# design.net
KiCad netlist of a schematic drawn in Altium Designer
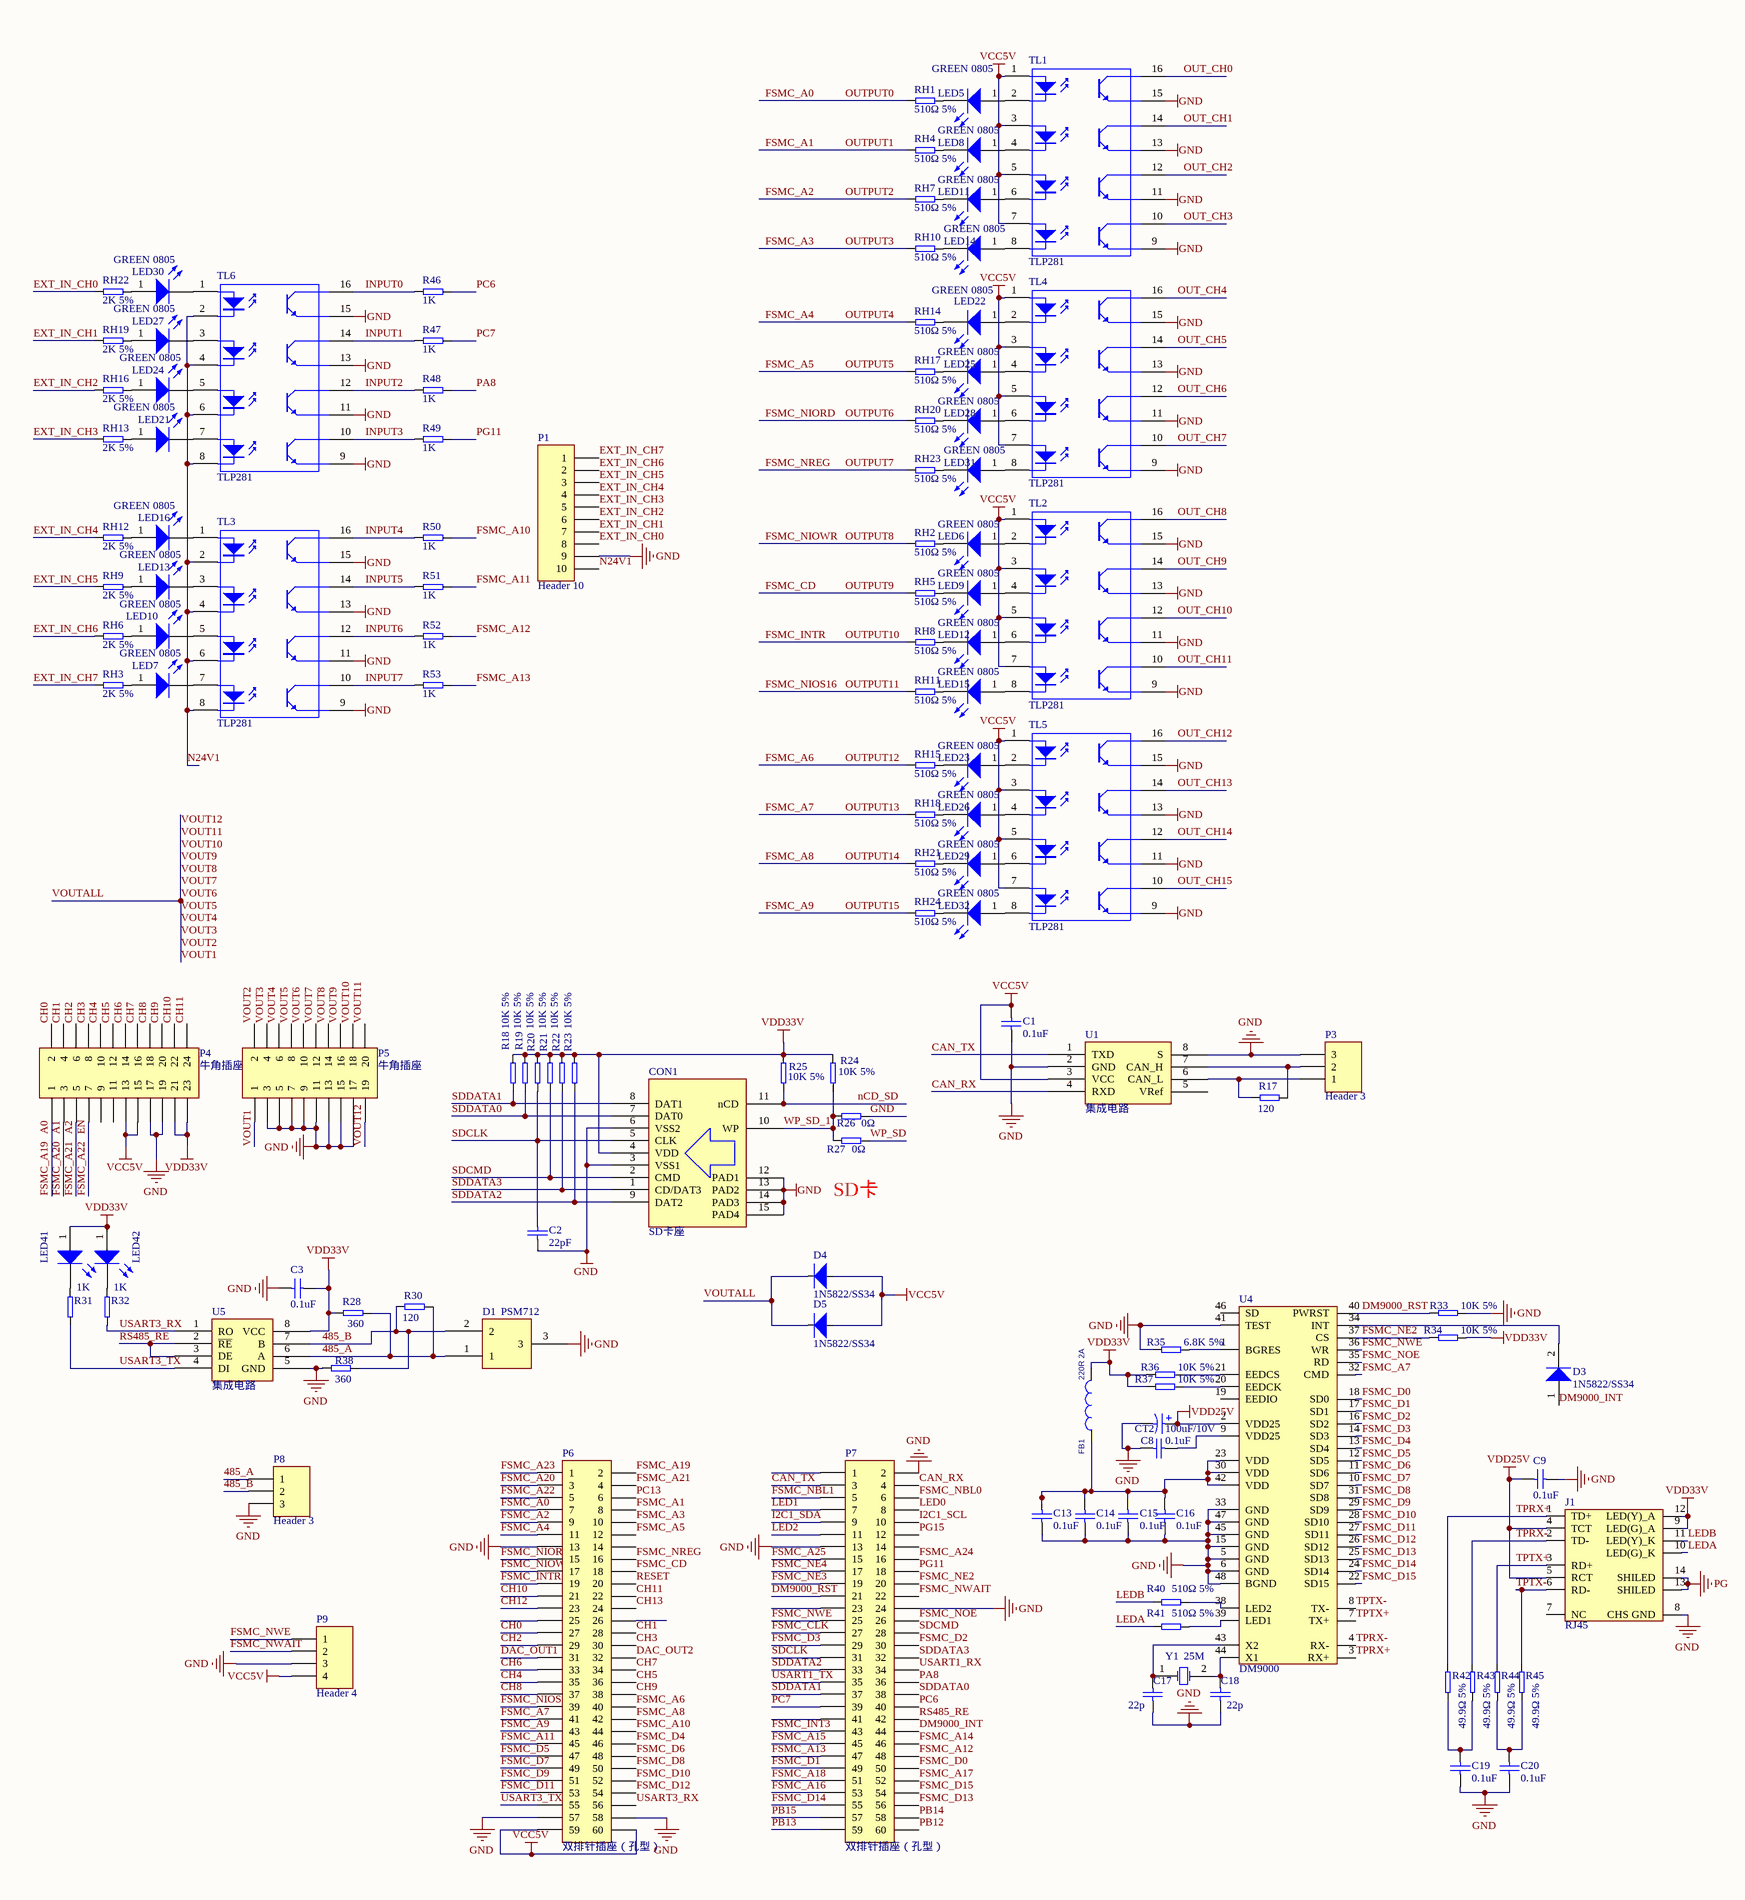
[diagram p0: 电眼主板.SchDoc, left]
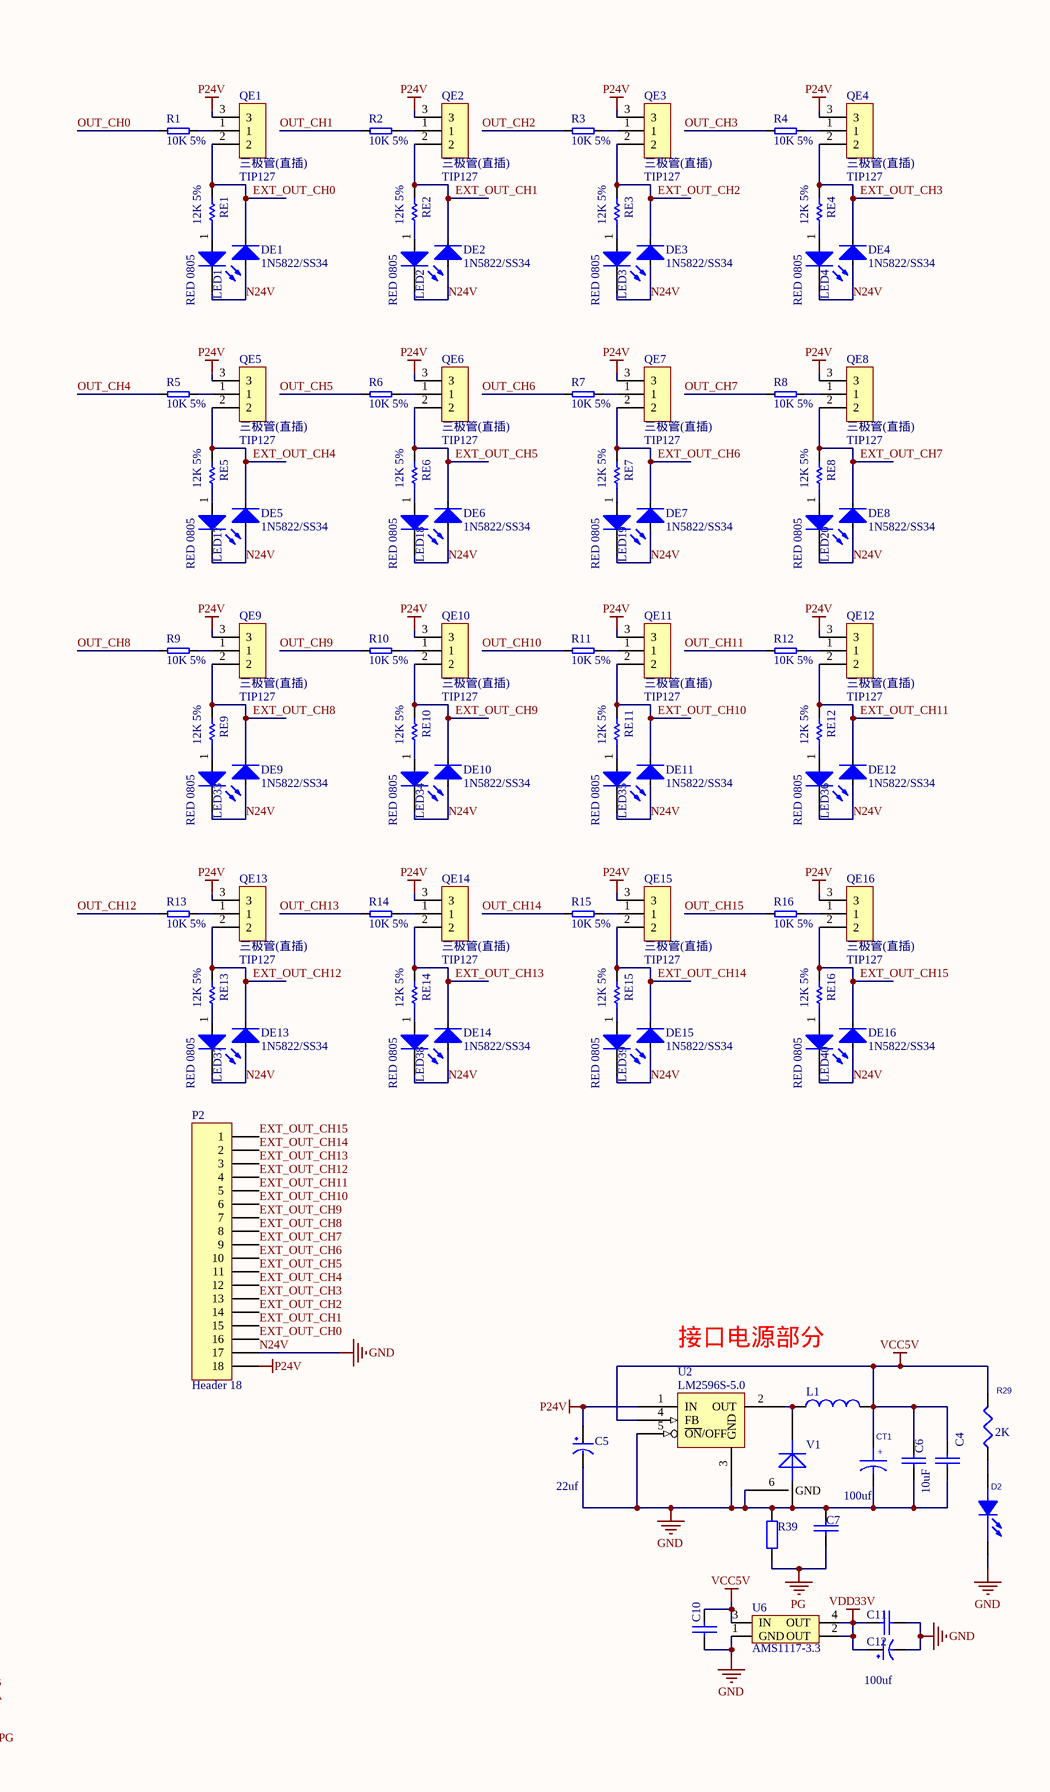
[diagram p1: 电眼主板.SchDoc, right]

(export (version "E")
  (design (tool "Eeschema 10.0.6"))
  (components
    (comp (ref "C1")
      (value "0.1uF")
      (footprint "0603")
      (description "0603X7R104J160NT(0.1uF)")
      (fields (field (name "Comment") "电容(贴片)"))
      (libsource (lib "altium-import") (part "root_3_CAP_0.1uF X7R 0603_"))
    )
    (comp (ref "C2")
      (value "22pF")
      (footprint "0603")
      (description "0603COG220J500NT(22pF)")
      (fields (field (name "Comment") "电容(贴片)"))
      (libsource (lib "altium-import") (part "root_1_CAP_22pF COG 0603_"))
    )
    (comp (ref "C3")
      (value "0.1uF")
      (footprint "0603")
      (description "0603X7R104J160NT(0.1uF)")
      (fields (field (name "Comment") "电容(贴片)"))
      (libsource (lib "altium-import") (part "root_0_CAP_0.1uF X7R 0603_"))
    )
    (comp (ref "C4")
      (value "电容(贴片)")
      (footprint "0805C")
      (description "'0603X7R104J160NT(0.1uF)")
      (libsource (lib "*") (part "CAP"))
    )
    (comp (ref "C5")
      (value "22uf")
      (footprint "CC6.56.5")
      (description "35TZV22M5X6.1")
      (fields (field (name "Comment") "电解电容(贴片)"))
      (libsource (lib "") (part "CAP_1"))
    )
    (comp (ref "C6")
      (value "10uF")
      (footprint "0805C")
      (description "片状电容")
      (libsource (lib "*") (part "Pro92D1.TMP_105_9"))
    )
    (comp (ref "C7") (value "102/2KV") (footprint "0805CC") (libsource (lib "*") (part "CAP")))
    (comp (ref "C8")
      (value "0.1uF")
      (footprint "0603")
      (description "0603X7R104J160NT(0.1uF)")
      (fields (field (name "Comment") "电容(贴片)"))
      (libsource (lib "altium-import") (part "root_0_mirrored_CAP_0.1uF X7R 0603_"))
    )
    (comp (ref "C9")
      (value "0.1uF")
      (footprint "0603")
      (description "0603X7R104J160NT(0.1uF)")
      (fields (field (name "Comment") "电容(贴片)"))
      (libsource (lib "altium-import") (part "root_2_CAP_0.1uF X7R 0603_"))
    )
    (comp (ref "C10")
      (value "电容(贴片)")
      (footprint "0805C")
      (description "'0603X7R104J160NT(0.1uF)")
      (libsource (lib "*") (part "CAP"))
    )
    (comp (ref "C11")
      (value "电容(贴片)")
      (footprint "0805C")
      (description "'0603X7R104J160NT(0.1uF)")
      (libsource (lib "*") (part "CAP"))
    )
    (comp (ref "C12")
      (value "100uf")
      (footprint "CC6.56.5")
      (description "10SEV100M6.3X5.5")
      (fields (field (name "Comment") "电解电容(贴片)"))
      (libsource (lib "WarShip V3 STM32103封装库") (part "CAP"))
    )
    (comp (ref "C13")
      (value "0.1uF")
      (footprint "0603")
      (description "0603X7R104J160NT(0.1uF)")
      (fields (field (name "Comment") "电容(贴片)"))
      (libsource (lib "altium-import") (part "root_1_CAP_0.1uF X7R 0603_"))
    )
    (comp (ref "C14")
      (value "0.1uF")
      (footprint "0603")
      (description "0603X7R104J160NT(0.1uF)")
      (fields (field (name "Comment") "电容(贴片)"))
      (libsource (lib "altium-import") (part "root_1_CAP_0.1uF X7R 0603_"))
    )
    (comp (ref "C15")
      (value "0.1uF")
      (footprint "0603")
      (description "0603X7R104J160NT(0.1uF)")
      (fields (field (name "Comment") "电容(贴片)"))
      (libsource (lib "altium-import") (part "root_1_CAP_0.1uF X7R 0603_"))
    )
    (comp (ref "C16")
      (value "0.1uF")
      (footprint "0603")
      (description "0603X7R104J160NT(0.1uF)")
      (fields (field (name "Comment") "电容(贴片)"))
      (libsource (lib "altium-import") (part "root_1_CAP_0.1uF X7R 0603_"))
    )
    (comp (ref "C17")
      (value "22p")
      (footprint "0603")
      (description "Capacitor 22p")
      (fields (field (name "Comment") "电容(贴片)") (field (name "PUBLISHER") "Altium Limited"))
      (libsource (lib "Miscellaneous Devices") (part "Cap"))
    )
    (comp (ref "C18")
      (value "22p")
      (footprint "0603")
      (description "Capacitor 22p")
      (fields (field (name "Comment") "电容(贴片)") (field (name "PUBLISHER") "Altium Limited"))
      (libsource (lib "Miscellaneous Devices") (part "Cap"))
    )
    (comp (ref "C19")
      (value "0.1uF")
      (footprint "0603")
      (description "0603X7R104J160NT(0.1uF)")
      (fields (field (name "Comment") "电容(贴片)"))
      (libsource (lib "altium-import") (part "root_1_CAP_0.1uF X7R 0603_"))
    )
    (comp (ref "C20")
      (value "0.1uF")
      (footprint "0603")
      (description "0603X7R104J160NT(0.1uF)")
      (fields (field (name "Comment") "电容(贴片)"))
      (libsource (lib "altium-import") (part "root_1_CAP_0.1uF X7R 0603_"))
    )
    (comp (ref "CON1")
      (value "SD卡座")
      (footprint "SDCARD")
      (description "SD/MMC CARD 26mm*25mm")
      (libsource (lib "altium-import") (part "root_0_SD-CARD_"))
    )
    (comp (ref "CT1")
      (value "100uf")
      (footprint "CT7343")
      (description "CAP TANTALUM 100UF 16V 20% SMD")
      (fields (field (name "VENDOR PART#") "495-2256-1-ND") (field (name "MFG PART#") "B45196H3107M409"))
      (libsource (lib "*") (part "CAP POL"))
    )
    (comp (ref "CT2")
      (value "100uF/10V")
      (footprint "6032")
      (description "CAP TANTALUM 100UF 16V 20% SMD")
      (fields (field (name "Comment") "钽电容"))
      (libsource (lib "altium-import") (part "root_1_mirrored_CAP TAN 100uF/10V/6032_"))
    )
    (comp (ref "D1") (value "PSM712") (footprint "SOT-23") (libsource (lib "PSM712") (part "Component_1")))
    (comp (ref "D2")
      (value "二极管(贴片发光红色)")
      (description "17-215-SURC-S530-A3-TR8")
      (fields (field (name "VENDOR PART#") "160-1426-1-ND") (field (name "MFG PART#") "LTST-C171KGKT"))
      (libsource (lib "*") (part "LED"))
    )
    (comp (ref "D3")
      (value "1N5822/SS34")
      (footprint "D1206")
      (description "1N4148/1206")
      (fields (field (name "Comment") "二极管(贴片)"))
      (libsource (lib "altium-import") (part "root_3_mirrored_DIODE 1N4148/1206_"))
    )
    (comp (ref "D4")
      (value "1N5822/SS34")
      (footprint "D1206")
      (description "1N5822/SS34/SMA 肖特基")
      (fields (field (name "Comment") "二极管(贴片)"))
      (libsource (lib "SCH_XIJUN") (part "DIODE 1N5822/SS34"))
    )
    (comp (ref "D5")
      (value "1N5822/SS34")
      (footprint "D1206")
      (description "1N5822/SS34/SMA 肖特基")
      (fields (field (name "Comment") "二极管(贴片)"))
      (libsource (lib "SCH_XIJUN") (part "DIODE 1N5822/SS34"))
    )
    (comp (ref "DE1")
      (value "1N5822/SS34")
      (footprint "D1206")
      (description "1N5822/SS34/SMA 肖特基")
      (fields (field (name "Comment") "二极管(贴片)"))
      (libsource (lib "SCH_XIJUN") (part "DIODE 1N5822/SS34"))
    )
    (comp (ref "DE2")
      (value "1N5822/SS34")
      (footprint "D1206")
      (description "1N5822/SS34/SMA 肖特基")
      (fields (field (name "Comment") "二极管(贴片)"))
      (libsource (lib "SCH_XIJUN") (part "DIODE 1N5822/SS34"))
    )
    (comp (ref "DE3")
      (value "1N5822/SS34")
      (footprint "D1206")
      (description "1N5822/SS34/SMA 肖特基")
      (fields (field (name "Comment") "二极管(贴片)"))
      (libsource (lib "SCH_XIJUN") (part "DIODE 1N5822/SS34"))
    )
    (comp (ref "DE4")
      (value "1N5822/SS34")
      (footprint "D1206")
      (description "1N5822/SS34/SMA 肖特基")
      (fields (field (name "Comment") "二极管(贴片)"))
      (libsource (lib "SCH_XIJUN") (part "DIODE 1N5822/SS34"))
    )
    (comp (ref "DE5")
      (value "1N5822/SS34")
      (footprint "D1206")
      (description "1N5822/SS34/SMA 肖特基")
      (fields (field (name "Comment") "二极管(贴片)"))
      (libsource (lib "SCH_XIJUN") (part "DIODE 1N5822/SS34"))
    )
    (comp (ref "DE6")
      (value "1N5822/SS34")
      (footprint "D1206")
      (description "1N5822/SS34/SMA 肖特基")
      (fields (field (name "Comment") "二极管(贴片)"))
      (libsource (lib "SCH_XIJUN") (part "DIODE 1N5822/SS34"))
    )
    (comp (ref "DE7")
      (value "1N5822/SS34")
      (footprint "D1206")
      (description "1N5822/SS34/SMA 肖特基")
      (fields (field (name "Comment") "二极管(贴片)"))
      (libsource (lib "SCH_XIJUN") (part "DIODE 1N5822/SS34"))
    )
    (comp (ref "DE8")
      (value "1N5822/SS34")
      (footprint "D1206")
      (description "1N5822/SS34/SMA 肖特基")
      (fields (field (name "Comment") "二极管(贴片)"))
      (libsource (lib "SCH_XIJUN") (part "DIODE 1N5822/SS34"))
    )
    (comp (ref "DE9")
      (value "1N5822/SS34")
      (footprint "D1206")
      (description "1N5822/SS34/SMA 肖特基")
      (fields (field (name "Comment") "二极管(贴片)"))
      (libsource (lib "SCH_XIJUN") (part "DIODE 1N5822/SS34"))
    )
    (comp (ref "DE10")
      (value "1N5822/SS34")
      (footprint "D1206")
      (description "1N5822/SS34/SMA 肖特基")
      (fields (field (name "Comment") "二极管(贴片)"))
      (libsource (lib "SCH_XIJUN") (part "DIODE 1N5822/SS34"))
    )
    (comp (ref "DE11")
      (value "1N5822/SS34")
      (footprint "D1206")
      (description "1N5822/SS34/SMA 肖特基")
      (fields (field (name "Comment") "二极管(贴片)"))
      (libsource (lib "SCH_XIJUN") (part "DIODE 1N5822/SS34"))
    )
    (comp (ref "DE12")
      (value "1N5822/SS34")
      (footprint "D1206")
      (description "1N5822/SS34/SMA 肖特基")
      (fields (field (name "Comment") "二极管(贴片)"))
      (libsource (lib "SCH_XIJUN") (part "DIODE 1N5822/SS34"))
    )
    (comp (ref "DE13")
      (value "1N5822/SS34")
      (footprint "D1206")
      (description "1N5822/SS34/SMA 肖特基")
      (fields (field (name "Comment") "二极管(贴片)"))
      (libsource (lib "SCH_XIJUN") (part "DIODE 1N5822/SS34"))
    )
    (comp (ref "DE14")
      (value "1N5822/SS34")
      (footprint "D1206")
      (description "1N5822/SS34/SMA 肖特基")
      (fields (field (name "Comment") "二极管(贴片)"))
      (libsource (lib "SCH_XIJUN") (part "DIODE 1N5822/SS34"))
    )
    (comp (ref "DE15")
      (value "1N5822/SS34")
      (footprint "D1206")
      (description "1N5822/SS34/SMA 肖特基")
      (fields (field (name "Comment") "二极管(贴片)"))
      (libsource (lib "SCH_XIJUN") (part "DIODE 1N5822/SS34"))
    )
    (comp (ref "DE16")
      (value "1N5822/SS34")
      (footprint "D1206")
      (description "1N5822/SS34/SMA 肖特基")
      (fields (field (name "Comment") "二极管(贴片)"))
      (libsource (lib "SCH_XIJUN") (part "DIODE 1N5822/SS34"))
    )
    (comp (ref "FB1")
      (value "220R 2A")
      (description "220R,2.0A,0.05DCR")
      (fields (field (name "MFG") "Murata") (field (name "MFG PART#") "BLM18PG121SN1D"))
      (libsource (lib "*") (part "FERRITE"))
    )
    (comp (ref "J1")
      (value "RJ45")
      (footprint "HR911105A")
      (description "HR911105A")
      (libsource (lib "WarShip V3 STM32103封装库") (part "HR911105"))
    )
    (comp (ref "L1")
      (value "电感(贴片)")
      (footprint "6045")
      (description "PRS6045-330MT")
      (fields (field (name "PUBLISHER") "Altium Limited"))
      (libsource (lib "Miscellaneous Devices") (part "Inductor"))
    )
    (comp (ref "LED1")
      (value "RED 0805")
      (footprint "LED-0805")
      (description "'17-215-SURC-S530-A3-TR8")
      (fields (field (name "Comment") "二极管(贴片发光红色)"))
      (libsource (lib "SCH_XIJUN") (part "LED_GREEN 0805"))
    )
    (comp (ref "LED2")
      (value "RED 0805")
      (footprint "LED-0805")
      (description "'17-215-SURC-S530-A3-TR8")
      (fields (field (name "Comment") "二极管(贴片发光红色)"))
      (libsource (lib "SCH_XIJUN") (part "LED_GREEN 0805"))
    )
    (comp (ref "LED3")
      (value "RED 0805")
      (footprint "LED-0805")
      (description "'17-215-SURC-S530-A3-TR8")
      (fields (field (name "Comment") "二极管(贴片发光红色)"))
      (libsource (lib "SCH_XIJUN") (part "LED_GREEN 0805"))
    )
    (comp (ref "LED4")
      (value "RED 0805")
      (footprint "LED-0805")
      (description "'17-215-SURC-S530-A3-TR8")
      (fields (field (name "Comment") "二极管(贴片发光红色)"))
      (libsource (lib "SCH_XIJUN") (part "LED_GREEN 0805"))
    )
    (comp (ref "LED5")
      (value "GREEN 0805")
      (footprint "LED-0805")
      (description "黄色LED")
      (fields (field (name "Comment") "二极管(贴片发光黄色)"))
      (libsource (lib "SCH_XIJUN") (part "LED_GREEN 0805"))
    )
    (comp (ref "LED6")
      (value "GREEN 0805")
      (footprint "LED-0805")
      (description "黄色LED")
      (fields (field (name "Comment") "二极管(贴片发光黄色)"))
      (libsource (lib "SCH_XIJUN") (part "LED_GREEN 0805"))
    )
    (comp (ref "LED7")
      (value "GREEN 0805")
      (footprint "LED-0805")
      (description "17-215SYGC-S530-E2-TR8")
      (fields (field (name "Comment") "二极管(贴片发光绿色)"))
      (libsource (lib "SCH_XIJUN") (part "LED_GREEN 0805"))
    )
    (comp (ref "LED8")
      (value "GREEN 0805")
      (footprint "LED-0805")
      (description "黄色LED")
      (fields (field (name "Comment") "二极管(贴片发光黄色)"))
      (libsource (lib "SCH_XIJUN") (part "LED_GREEN 0805"))
    )
    (comp (ref "LED9")
      (value "GREEN 0805")
      (footprint "LED-0805")
      (description "黄色LED")
      (fields (field (name "Comment") "二极管(贴片发光黄色)"))
      (libsource (lib "SCH_XIJUN") (part "LED_GREEN 0805"))
    )
    (comp (ref "LED10")
      (value "GREEN 0805")
      (footprint "LED-0805")
      (description "17-215SYGC-S530-E2-TR8")
      (fields (field (name "Comment") "二极管(贴片发光绿色)"))
      (libsource (lib "SCH_XIJUN") (part "LED_GREEN 0805"))
    )
    (comp (ref "LED11")
      (value "GREEN 0805")
      (footprint "LED-0805")
      (description "黄色LED")
      (fields (field (name "Comment") "二极管(贴片发光黄色)"))
      (libsource (lib "SCH_XIJUN") (part "LED_GREEN 0805"))
    )
    (comp (ref "LED12")
      (value "GREEN 0805")
      (footprint "LED-0805")
      (description "黄色LED")
      (fields (field (name "Comment") "二极管(贴片发光黄色)"))
      (libsource (lib "SCH_XIJUN") (part "LED_GREEN 0805"))
    )
    (comp (ref "LED13")
      (value "GREEN 0805")
      (footprint "LED-0805")
      (description "17-215SYGC-S530-E2-TR8")
      (fields (field (name "Comment") "二极管(贴片发光绿色)"))
      (libsource (lib "SCH_XIJUN") (part "LED_GREEN 0805"))
    )
    (comp (ref "LED14")
      (value "GREEN 0805")
      (footprint "LED-0805")
      (description "黄色LED")
      (fields (field (name "Comment") "二极管(贴片发光黄色)"))
      (libsource (lib "SCH_XIJUN") (part "LED_GREEN 0805"))
    )
    (comp (ref "LED15")
      (value "GREEN 0805")
      (footprint "LED-0805")
      (description "黄色LED")
      (fields (field (name "Comment") "二极管(贴片发光黄色)"))
      (libsource (lib "SCH_XIJUN") (part "LED_GREEN 0805"))
    )
    (comp (ref "LED16")
      (value "GREEN 0805")
      (footprint "LED-0805")
      (description "17-215SYGC-S530-E2-TR8")
      (fields (field (name "Comment") "二极管(贴片发光绿色)"))
      (libsource (lib "SCH_XIJUN") (part "LED_GREEN 0805"))
    )
    (comp (ref "LED17")
      (value "RED 0805")
      (footprint "LED-0805")
      (description "'17-215-SURC-S530-A3-TR8")
      (fields (field (name "Comment") "二极管(贴片发光红色)"))
      (libsource (lib "SCH_XIJUN") (part "LED_GREEN 0805"))
    )
    (comp (ref "LED18")
      (value "RED 0805")
      (footprint "LED-0805")
      (description "'17-215-SURC-S530-A3-TR8")
      (fields (field (name "Comment") "二极管(贴片发光红色)"))
      (libsource (lib "SCH_XIJUN") (part "LED_GREEN 0805"))
    )
    (comp (ref "LED19")
      (value "RED 0805")
      (footprint "LED-0805")
      (description "'17-215-SURC-S530-A3-TR8")
      (fields (field (name "Comment") "二极管(贴片发光红色)"))
      (libsource (lib "SCH_XIJUN") (part "LED_GREEN 0805"))
    )
    (comp (ref "LED20")
      (value "RED 0805")
      (footprint "LED-0805")
      (description "'17-215-SURC-S530-A3-TR8")
      (fields (field (name "Comment") "二极管(贴片发光红色)"))
      (libsource (lib "SCH_XIJUN") (part "LED_GREEN 0805"))
    )
    (comp (ref "LED21")
      (value "GREEN 0805")
      (footprint "LED-0805")
      (description "17-215SYGC-S530-E2-TR8")
      (fields (field (name "Comment") "二极管(贴片发光绿色)"))
      (libsource (lib "SCH_XIJUN") (part "LED_GREEN 0805"))
    )
    (comp (ref "LED22")
      (value "GREEN 0805")
      (footprint "LED-0805")
      (description "黄色LED")
      (fields (field (name "Comment") "二极管(贴片发光黄色)"))
      (libsource (lib "SCH_XIJUN") (part "LED_GREEN 0805"))
    )
    (comp (ref "LED23")
      (value "GREEN 0805")
      (footprint "LED-0805")
      (description "黄色LED")
      (fields (field (name "Comment") "二极管(贴片发光黄色)"))
      (libsource (lib "SCH_XIJUN") (part "LED_GREEN 0805"))
    )
    (comp (ref "LED24")
      (value "GREEN 0805")
      (footprint "LED-0805")
      (description "17-215SYGC-S530-E2-TR8")
      (fields (field (name "Comment") "二极管(贴片发光绿色)"))
      (libsource (lib "SCH_XIJUN") (part "LED_GREEN 0805"))
    )
    (comp (ref "LED25")
      (value "GREEN 0805")
      (footprint "LED-0805")
      (description "黄色LED")
      (fields (field (name "Comment") "二极管(贴片发光黄色)"))
      (libsource (lib "SCH_XIJUN") (part "LED_GREEN 0805"))
    )
    (comp (ref "LED26")
      (value "GREEN 0805")
      (footprint "LED-0805")
      (description "黄色LED")
      (fields (field (name "Comment") "二极管(贴片发光黄色)"))
      (libsource (lib "SCH_XIJUN") (part "LED_GREEN 0805"))
    )
    (comp (ref "LED27")
      (value "GREEN 0805")
      (footprint "LED-0805")
      (description "17-215SYGC-S530-E2-TR8")
      (fields (field (name "Comment") "二极管(贴片发光绿色)"))
      (libsource (lib "SCH_XIJUN") (part "LED_GREEN 0805"))
    )
    (comp (ref "LED28")
      (value "GREEN 0805")
      (footprint "LED-0805")
      (description "黄色LED")
      (fields (field (name "Comment") "二极管(贴片发光黄色)"))
      (libsource (lib "SCH_XIJUN") (part "LED_GREEN 0805"))
    )
    (comp (ref "LED29")
      (value "GREEN 0805")
      (footprint "LED-0805")
      (description "黄色LED")
      (fields (field (name "Comment") "二极管(贴片发光黄色)"))
      (libsource (lib "SCH_XIJUN") (part "LED_GREEN 0805"))
    )
    (comp (ref "LED30")
      (value "GREEN 0805")
      (footprint "LED-0805")
      (description "17-215SYGC-S530-E2-TR8")
      (fields (field (name "Comment") "二极管(贴片发光绿色)"))
      (libsource (lib "SCH_XIJUN") (part "LED_GREEN 0805"))
    )
    (comp (ref "LED31")
      (value "GREEN 0805")
      (footprint "LED-0805")
      (description "黄色LED")
      (fields (field (name "Comment") "二极管(贴片发光黄色)"))
      (libsource (lib "SCH_XIJUN") (part "LED_GREEN 0805"))
    )
    (comp (ref "LED32")
      (value "GREEN 0805")
      (footprint "LED-0805")
      (description "黄色LED")
      (fields (field (name "Comment") "二极管(贴片发光黄色)"))
      (libsource (lib "SCH_XIJUN") (part "LED_GREEN 0805"))
    )
    (comp (ref "LED33")
      (value "RED 0805")
      (footprint "LED-0805")
      (description "'17-215-SURC-S530-A3-TR8")
      (fields (field (name "Comment") "二极管(贴片发光红色)"))
      (libsource (lib "SCH_XIJUN") (part "LED_GREEN 0805"))
    )
    (comp (ref "LED34")
      (value "RED 0805")
      (footprint "LED-0805")
      (description "'17-215-SURC-S530-A3-TR8")
      (fields (field (name "Comment") "二极管(贴片发光红色)"))
      (libsource (lib "SCH_XIJUN") (part "LED_GREEN 0805"))
    )
    (comp (ref "LED35")
      (value "RED 0805")
      (footprint "LED-0805")
      (description "'17-215-SURC-S530-A3-TR8")
      (fields (field (name "Comment") "二极管(贴片发光红色)"))
      (libsource (lib "SCH_XIJUN") (part "LED_GREEN 0805"))
    )
    (comp (ref "LED36")
      (value "RED 0805")
      (footprint "LED-0805")
      (description "'17-215-SURC-S530-A3-TR8")
      (fields (field (name "Comment") "二极管(贴片发光红色)"))
      (libsource (lib "SCH_XIJUN") (part "LED_GREEN 0805"))
    )
    (comp (ref "LED37")
      (value "RED 0805")
      (footprint "LED-0805")
      (description "'17-215-SURC-S530-A3-TR8")
      (fields (field (name "Comment") "二极管(贴片发光红色)"))
      (libsource (lib "SCH_XIJUN") (part "LED_GREEN 0805"))
    )
    (comp (ref "LED38")
      (value "RED 0805")
      (footprint "LED-0805")
      (description "'17-215-SURC-S530-A3-TR8")
      (fields (field (name "Comment") "二极管(贴片发光红色)"))
      (libsource (lib "SCH_XIJUN") (part "LED_GREEN 0805"))
    )
    (comp (ref "LED39")
      (value "RED 0805")
      (footprint "LED-0805")
      (description "'17-215-SURC-S530-A3-TR8")
      (fields (field (name "Comment") "二极管(贴片发光红色)"))
      (libsource (lib "SCH_XIJUN") (part "LED_GREEN 0805"))
    )
    (comp (ref "LED40")
      (value "RED 0805")
      (footprint "LED-0805")
      (description "'17-215-SURC-S530-A3-TR8")
      (fields (field (name "Comment") "二极管(贴片发光红色)"))
      (libsource (lib "SCH_XIJUN") (part "LED_GREEN 0805"))
    )
    (comp (ref "LED41")
      (value "二极管(贴片发光绿色)")
      (footprint "LED-0805")
      (description "17-215SYGC-S530-E2-TR8")
      (libsource (lib "SCH_XIJUN") (part "LED_GREEN 0805"))
    )
    (comp (ref "LED42")
      (value "二极管(贴片发光绿色)")
      (footprint "LED-0805")
      (description "17-215SYGC-S530-E2-TR8")
      (libsource (lib "SCH_XIJUN") (part "LED_GREEN 0805"))
    )
    (comp (ref "P1")
      (value "Header 10")
      (footprint "CON10")
      (description "Header, 10-Pin")
      (fields (field (name "PUBLISHER") "Altium Limited"))
      (libsource (lib "Miscellaneous Connectors") (part "Header 10"))
    )
    (comp (ref "P2")
      (value "Header 18")
      (footprint "CON18")
      (description "Header, 18-Pin")
      (fields (field (name "PUBLISHER") "Altium Limited"))
      (libsource (lib "Miscellaneous Connectors") (part "Header 18"))
    )
    (comp (ref "P3")
      (value "Header 3")
      (footprint "CON3")
      (description "Header, 3-Pin")
      (fields (field (name "PUBLISHER") "Altium Limited"))
      (libsource (lib "") (part "Header 3_1"))
    )
    (comp (ref "P4")
      (value "牛角插座")
      (footprint "niujiaocha24P")
      (description "Header, 12-Pin, Dual row")
      (fields (field (name "PUBLISHER") "Altium Limited"))
      (libsource (lib "Miscellaneous Connectors") (part "Header 12X2"))
    )
    (comp (ref "P5")
      (value "牛角插座")
      (footprint "niujiaocha20p")
      (description "Header, 10-Pin, Dual row")
      (fields (field (name "PUBLISHER") "Altium Limited"))
      (libsource (lib "Miscellaneous Connectors") (part "Header 10X2"))
    )
    (comp (ref "P6")
      (value "双排针插座（孔型）")
      (footprint "HDR2X30")
      (description "双排 30*2P 脚间距 2.54mm")
      (fields (field (name "PUBLISHER") "Altium Limited"))
      (libsource (lib "Miscellaneous Connectors") (part "Header 30X2"))
    )
    (comp (ref "P7")
      (value "双排针插座（孔型）")
      (footprint "HDR2X30")
      (description "双排 30*2P 脚间距 2.54mm")
      (fields (field (name "PUBLISHER") "Altium Limited"))
      (libsource (lib "Miscellaneous Connectors") (part "Header 30X2"))
    )
    (comp (ref "P8")
      (value "Header 3")
      (footprint "CON3")
      (description "Header, 3-Pin")
      (fields (field (name "PUBLISHER") "Altium Limited"))
      (libsource (lib "Miscellaneous Connectors") (part "Header 3"))
    )
    (comp (ref "P9")
      (value "Header 4")
      (footprint "con4")
      (description "Header, 4-Pin")
      (fields (field (name "PUBLISHER") "Altium Limited"))
      (libsource (lib "Miscellaneous Connectors") (part "Header 4"))
    )
    (comp (ref "QE1")
      (value "三极管(直插)")
      (footprint "TIP127")
      (fields (field (name "ALTIUM_VALUE") "TIP127"))
      (libsource (lib "MYlib") (part "TIP127"))
    )
    (comp (ref "QE2")
      (value "三极管(直插)")
      (footprint "TIP127")
      (fields (field (name "ALTIUM_VALUE") "TIP127"))
      (libsource (lib "MYlib") (part "TIP127"))
    )
    (comp (ref "QE3")
      (value "三极管(直插)")
      (footprint "TIP127")
      (fields (field (name "ALTIUM_VALUE") "TIP127"))
      (libsource (lib "MYlib") (part "TIP127"))
    )
    (comp (ref "QE4")
      (value "三极管(直插)")
      (footprint "TIP127")
      (fields (field (name "ALTIUM_VALUE") "TIP127"))
      (libsource (lib "MYlib") (part "TIP127"))
    )
    (comp (ref "QE5")
      (value "三极管(直插)")
      (footprint "TIP127")
      (fields (field (name "ALTIUM_VALUE") "TIP127"))
      (libsource (lib "MYlib") (part "TIP127"))
    )
    (comp (ref "QE6")
      (value "三极管(直插)")
      (footprint "TIP127")
      (fields (field (name "ALTIUM_VALUE") "TIP127"))
      (libsource (lib "MYlib") (part "TIP127"))
    )
    (comp (ref "QE7")
      (value "三极管(直插)")
      (footprint "TIP127")
      (fields (field (name "ALTIUM_VALUE") "TIP127"))
      (libsource (lib "MYlib") (part "TIP127"))
    )
    (comp (ref "QE8")
      (value "三极管(直插)")
      (footprint "TIP127")
      (fields (field (name "ALTIUM_VALUE") "TIP127"))
      (libsource (lib "MYlib") (part "TIP127"))
    )
    (comp (ref "QE9")
      (value "三极管(直插)")
      (footprint "TIP127")
      (fields (field (name "ALTIUM_VALUE") "TIP127"))
      (libsource (lib "MYlib") (part "TIP127"))
    )
    (comp (ref "QE10")
      (value "三极管(直插)")
      (footprint "TIP127")
      (fields (field (name "ALTIUM_VALUE") "TIP127"))
      (libsource (lib "MYlib") (part "TIP127"))
    )
    (comp (ref "QE11")
      (value "三极管(直插)")
      (footprint "TIP127")
      (fields (field (name "ALTIUM_VALUE") "TIP127"))
      (libsource (lib "MYlib") (part "TIP127"))
    )
    (comp (ref "QE12")
      (value "三极管(直插)")
      (footprint "TIP127")
      (fields (field (name "ALTIUM_VALUE") "TIP127"))
      (libsource (lib "MYlib") (part "TIP127"))
    )
    (comp (ref "QE13")
      (value "三极管(直插)")
      (footprint "TIP127")
      (fields (field (name "ALTIUM_VALUE") "TIP127"))
      (libsource (lib "MYlib") (part "TIP127"))
    )
    (comp (ref "QE14")
      (value "三极管(直插)")
      (footprint "TIP127")
      (fields (field (name "ALTIUM_VALUE") "TIP127"))
      (libsource (lib "MYlib") (part "TIP127"))
    )
    (comp (ref "QE15")
      (value "三极管(直插)")
      (footprint "TIP127")
      (fields (field (name "ALTIUM_VALUE") "TIP127"))
      (libsource (lib "MYlib") (part "TIP127"))
    )
    (comp (ref "QE16")
      (value "三极管(直插)")
      (footprint "TIP127")
      (fields (field (name "ALTIUM_VALUE") "TIP127"))
      (libsource (lib "MYlib") (part "TIP127"))
    )
    (comp (ref "R1")
      (value "10K 5%")
      (footprint "0603")
      (description "RS-03K-103±5%(10KΩ)")
      (fields (field (name "Comment") "电阻(贴片)"))
      (libsource (lib "altium-import") (part "root_0_RES_10K 5% 0603_"))
    )
    (comp (ref "R2")
      (value "10K 5%")
      (footprint "0603")
      (description "RS-03K-103±5%(10KΩ)")
      (fields (field (name "Comment") "电阻(贴片)"))
      (libsource (lib "altium-import") (part "root_0_RES_10K 5% 0603_"))
    )
    (comp (ref "R3")
      (value "10K 5%")
      (footprint "0603")
      (description "RS-03K-103±5%(10KΩ)")
      (fields (field (name "Comment") "电阻(贴片)"))
      (libsource (lib "altium-import") (part "root_0_RES_10K 5% 0603_"))
    )
    (comp (ref "R4")
      (value "10K 5%")
      (footprint "0603")
      (description "RS-03K-103±5%(10KΩ)")
      (fields (field (name "Comment") "电阻(贴片)"))
      (libsource (lib "altium-import") (part "root_0_RES_10K 5% 0603_"))
    )
    (comp (ref "R5")
      (value "10K 5%")
      (footprint "0603")
      (description "RS-03K-103±5%(10KΩ)")
      (fields (field (name "Comment") "电阻(贴片)"))
      (libsource (lib "altium-import") (part "root_0_RES_10K 5% 0603_"))
    )
    (comp (ref "R6")
      (value "10K 5%")
      (footprint "0603")
      (description "RS-03K-103±5%(10KΩ)")
      (fields (field (name "Comment") "电阻(贴片)"))
      (libsource (lib "altium-import") (part "root_0_RES_10K 5% 0603_"))
    )
    (comp (ref "R7")
      (value "10K 5%")
      (footprint "0603")
      (description "RS-03K-103±5%(10KΩ)")
      (fields (field (name "Comment") "电阻(贴片)"))
      (libsource (lib "altium-import") (part "root_0_RES_10K 5% 0603_"))
    )
    (comp (ref "R8")
      (value "10K 5%")
      (footprint "0603")
      (description "RS-03K-103±5%(10KΩ)")
      (fields (field (name "Comment") "电阻(贴片)"))
      (libsource (lib "altium-import") (part "root_0_RES_10K 5% 0603_"))
    )
    (comp (ref "R9")
      (value "10K 5%")
      (footprint "0603")
      (description "RS-03K-103±5%(10KΩ)")
      (fields (field (name "Comment") "电阻(贴片)"))
      (libsource (lib "altium-import") (part "root_0_RES_10K 5% 0603_"))
    )
    (comp (ref "R10")
      (value "10K 5%")
      (footprint "0603")
      (description "RS-03K-103±5%(10KΩ)")
      (fields (field (name "Comment") "电阻(贴片)"))
      (libsource (lib "altium-import") (part "root_0_RES_10K 5% 0603_"))
    )
    (comp (ref "R11")
      (value "10K 5%")
      (footprint "0603")
      (description "RS-03K-103±5%(10KΩ)")
      (fields (field (name "Comment") "电阻(贴片)"))
      (libsource (lib "altium-import") (part "root_0_RES_10K 5% 0603_"))
    )
    (comp (ref "R12")
      (value "10K 5%")
      (footprint "0603")
      (description "RS-03K-103±5%(10KΩ)")
      (fields (field (name "Comment") "电阻(贴片)"))
      (libsource (lib "altium-import") (part "root_0_RES_10K 5% 0603_"))
    )
    (comp (ref "R13")
      (value "10K 5%")
      (footprint "0603")
      (description "RS-03K-103±5%(10KΩ)")
      (fields (field (name "Comment") "电阻(贴片)"))
      (libsource (lib "altium-import") (part "root_0_RES_10K 5% 0603_"))
    )
    (comp (ref "R14")
      (value "10K 5%")
      (footprint "0603")
      (description "RS-03K-103±5%(10KΩ)")
      (fields (field (name "Comment") "电阻(贴片)"))
      (libsource (lib "altium-import") (part "root_0_RES_10K 5% 0603_"))
    )
    (comp (ref "R15")
      (value "10K 5%")
      (footprint "0603")
      (description "RS-03K-103±5%(10KΩ)")
      (fields (field (name "Comment") "电阻(贴片)"))
      (libsource (lib "altium-import") (part "root_0_RES_10K 5% 0603_"))
    )
    (comp (ref "R16")
      (value "10K 5%")
      (footprint "0603")
      (description "RS-03K-103±5%(10KΩ)")
      (fields (field (name "Comment") "电阻(贴片)"))
      (libsource (lib "altium-import") (part "root_0_RES_10K 5% 0603_"))
    )
    (comp (ref "R17")
      (value "120")
      (footprint "0603")
      (description "RS-03K-102±5%(1KΩ)")
      (fields (field (name "Comment") "电阻(贴片)"))
      (libsource (lib "SCH_XIJUN") (part "RES_1K  5% 0603"))
    )
    (comp (ref "R18")
      (value "10K 5%")
      (footprint "0603")
      (description "RS-03K-103±5%(10KΩ)")
      (fields (field (name "Comment") "电阻(贴片)"))
      (libsource (lib "altium-import") (part "root_3_RES_10K 5% 0603_"))
    )
    (comp (ref "R19")
      (value "10K 5%")
      (footprint "0603")
      (description "RS-03K-103±5%(10KΩ)")
      (fields (field (name "Comment") "电阻(贴片)"))
      (libsource (lib "altium-import") (part "root_3_RES_10K 5% 0603_"))
    )
    (comp (ref "R20")
      (value "10K 5%")
      (footprint "0603")
      (description "RS-03K-103±5%(10KΩ)")
      (fields (field (name "Comment") "电阻(贴片)"))
      (libsource (lib "altium-import") (part "root_3_RES_10K 5% 0603_"))
    )
    (comp (ref "R21")
      (value "10K 5%")
      (footprint "0603")
      (description "RS-03K-103±5%(10KΩ)")
      (fields (field (name "Comment") "电阻(贴片)"))
      (libsource (lib "altium-import") (part "root_3_RES_10K 5% 0603_"))
    )
    (comp (ref "R22")
      (value "10K 5%")
      (footprint "0603")
      (description "RS-03K-103±5%(10KΩ)")
      (fields (field (name "Comment") "电阻(贴片)"))
      (libsource (lib "altium-import") (part "root_3_RES_10K 5% 0603_"))
    )
    (comp (ref "R23")
      (value "10K 5%")
      (footprint "0603")
      (description "RS-03K-103±5%(10KΩ)")
      (fields (field (name "Comment") "电阻(贴片)"))
      (libsource (lib "altium-import") (part "root_3_RES_10K 5% 0603_"))
    )
    (comp (ref "R24")
      (value "10K 5%")
      (footprint "0603")
      (description "RS-03K-103±5%(10KΩ)")
      (fields (field (name "Comment") "电阻(贴片)"))
      (libsource (lib "altium-import") (part "root_3_RES_10K 5% 0603_"))
    )
    (comp (ref "R25")
      (value "10K 5%")
      (footprint "0603")
      (description "RS-03K-103±5%(10KΩ)")
      (fields (field (name "Comment") "电阻(贴片)"))
      (libsource (lib "altium-import") (part "root_3_RES_10K 5% 0603_"))
    )
    (comp (ref "R26")
      (value "0Ω")
      (footprint "0603")
      (description "RS-03K-000±5%(0Ω)")
      (fields (field (name "Comment") "电阻(贴片)"))
      (libsource (lib "altium-import") (part "root_0_RES_0Ω 5% 0603_"))
    )
    (comp (ref "R27")
      (value "0Ω")
      (footprint "0603")
      (description "RS-03K-000±5%(0Ω)")
      (fields (field (name "Comment") "电阻(贴片)"))
      (libsource (lib "altium-import") (part "root_0_RES_0Ω 5% 0603_"))
    )
    (comp (ref "R28")
      (value "360")
      (footprint "0603")
      (description "RS-03K-102±5%(1KΩ)")
      (fields (field (name "Comment") "电阻(贴片)"))
      (libsource (lib "SCH_XIJUN") (part "RES_1K  5% 0603"))
    )
    (comp (ref "R29")
      (value "2K")
      (description "电阻(贴片)")
      (fields (field (name "VENDOR PART#") "P2.2KJCT-ND") (field (name "MFG PART#") "ERJ-2GEJ222X"))
      (libsource (lib "*") (part "RESISTOR_Dup1"))
    )
    (comp (ref "R30")
      (value "120")
      (footprint "0603")
      (description "RS-03K-102±5%(1KΩ)")
      (fields (field (name "Comment") "电阻(贴片)"))
      (libsource (lib "SCH_XIJUN") (part "RES_1K  5% 0603"))
    )
    (comp (ref "R31")
      (value "1K")
      (footprint "0805")
      (description "RS-03K-102±5%(1KΩ)")
      (fields (field (name "Comment") "电阻(贴片)"))
      (libsource (lib "SCH_XIJUN") (part "RES_1K  5% 0603"))
    )
    (comp (ref "R32")
      (value "1K")
      (footprint "0805")
      (description "RS-03K-102±5%(1KΩ)")
      (fields (field (name "Comment") "电阻(贴片)"))
      (libsource (lib "SCH_XIJUN") (part "RES_1K  5% 0603"))
    )
    (comp (ref "R33")
      (value "10K 5%")
      (footprint "0603")
      (description "RS-03K-103±5%(10KΩ)")
      (fields (field (name "Comment") "电阻(贴片)"))
      (libsource (lib "altium-import") (part "root_0_RES_10K 5% 0603_"))
    )
    (comp (ref "R34")
      (value "10K 5%")
      (footprint "0603")
      (description "RS-03K-103±5%(10KΩ)")
      (fields (field (name "Comment") "电阻(贴片)"))
      (libsource (lib "altium-import") (part "root_0_RES_10K 5% 0603_"))
    )
    (comp (ref "R35")
      (value "6.8K 5%")
      (footprint "0603")
      (description "RS-03K-103±5%(10KΩ)")
      (fields (field (name "Comment") "电阻(贴片)"))
      (libsource (lib "altium-import") (part "root_0_RES_10K 5% 0603_"))
    )
    (comp (ref "R36")
      (value "10K 5%")
      (footprint "0603")
      (description "RS-03K-103±5%(10KΩ)")
      (fields (field (name "Comment") "电阻(贴片)"))
      (libsource (lib "altium-import") (part "root_0_RES_10K 5% 0603_"))
    )
    (comp (ref "R37")
      (value "10K 5%")
      (footprint "0603")
      (description "RS-03K-103±5%(10KΩ)")
      (fields (field (name "Comment") "电阻(贴片)"))
      (libsource (lib "altium-import") (part "root_0_RES_10K 5% 0603_"))
    )
    (comp (ref "R38")
      (value "360")
      (footprint "0603")
      (description "RS-03K-102±5%(1KΩ)")
      (fields (field (name "Comment") "电阻(贴片)"))
      (libsource (lib "SCH_XIJUN") (part "RES_1K  5% 0603"))
    )
    (comp (ref "R39")
      (value "电阻(贴片)")
      (footprint "0805R")
      (description "Resistor")
      (fields (field (name "PUBLISHER") "Altium Limited"))
      (libsource (lib "My Library") (part "Res2"))
    )
    (comp (ref "R40")
      (value "510Ω 5%")
      (footprint "0603")
      (description "RS-03K-49.9±5%(49.9Ω)")
      (fields (field (name "Comment") "电阻(贴片)"))
      (libsource (lib "altium-import") (part "root_2_RES_49.9Ω 5% 0603_"))
    )
    (comp (ref "R41")
      (value "510Ω 5%")
      (footprint "0603")
      (description "RS-03K-49.9±5%(49.9Ω)")
      (fields (field (name "Comment") "电阻(贴片)"))
      (libsource (lib "altium-import") (part "root_2_RES_49.9Ω 5% 0603_"))
    )
    (comp (ref "R42")
      (value "49.9Ω 5%")
      (footprint "0603")
      (description "RS-03K-49.9±5%(49.9Ω)")
      (fields (field (name "Comment") "电阻(贴片)"))
      (libsource (lib "altium-import") (part "root_1_RES_49.9Ω 5% 0603_"))
    )
    (comp (ref "R43")
      (value "49.9Ω 5%")
      (footprint "0603")
      (description "RS-03K-49.9±5%(49.9Ω)")
      (fields (field (name "Comment") "电阻(贴片)"))
      (libsource (lib "altium-import") (part "root_1_RES_49.9Ω 5% 0603_"))
    )
    (comp (ref "R44")
      (value "49.9Ω 5%")
      (footprint "0603")
      (description "RS-03K-49.9±5%(49.9Ω)")
      (fields (field (name "Comment") "电阻(贴片)"))
      (libsource (lib "altium-import") (part "root_1_RES_49.9Ω 5% 0603_"))
    )
    (comp (ref "R45")
      (value "49.9Ω 5%")
      (footprint "0603")
      (description "RS-03K-49.9±5%(49.9Ω)")
      (fields (field (name "Comment") "电阻(贴片)"))
      (libsource (lib "altium-import") (part "root_1_RES_49.9Ω 5% 0603_"))
    )
    (comp (ref "R46")
      (value "1K")
      (footprint "0603")
      (description "RS-03K-102±5%(1KΩ)")
      (fields (field (name "Comment") "电阻(贴片)"))
      (libsource (lib "SCH_XIJUN") (part "RES_1K  5% 0603"))
    )
    (comp (ref "R47")
      (value "1K")
      (footprint "0603")
      (description "RS-03K-102±5%(1KΩ)")
      (fields (field (name "Comment") "电阻(贴片)"))
      (libsource (lib "SCH_XIJUN") (part "RES_1K  5% 0603"))
    )
    (comp (ref "R48")
      (value "1K")
      (footprint "0603")
      (description "RS-03K-102±5%(1KΩ)")
      (fields (field (name "Comment") "电阻(贴片)"))
      (libsource (lib "SCH_XIJUN") (part "RES_1K  5% 0603"))
    )
    (comp (ref "R49")
      (value "1K")
      (footprint "0603")
      (description "RS-03K-102±5%(1KΩ)")
      (fields (field (name "Comment") "电阻(贴片)"))
      (libsource (lib "SCH_XIJUN") (part "RES_1K  5% 0603"))
    )
    (comp (ref "R50")
      (value "1K")
      (footprint "0603")
      (description "RS-03K-102±5%(1KΩ)")
      (fields (field (name "Comment") "电阻(贴片)"))
      (libsource (lib "SCH_XIJUN") (part "RES_1K  5% 0603"))
    )
    (comp (ref "R51")
      (value "1K")
      (footprint "0603")
      (description "RS-03K-102±5%(1KΩ)")
      (fields (field (name "Comment") "电阻(贴片)"))
      (libsource (lib "SCH_XIJUN") (part "RES_1K  5% 0603"))
    )
    (comp (ref "R52")
      (value "1K")
      (footprint "0603")
      (description "RS-03K-102±5%(1KΩ)")
      (fields (field (name "Comment") "电阻(贴片)"))
      (libsource (lib "SCH_XIJUN") (part "RES_1K  5% 0603"))
    )
    (comp (ref "R53")
      (value "1K")
      (footprint "0603")
      (description "RS-03K-102±5%(1KΩ)")
      (fields (field (name "Comment") "电阻(贴片)"))
      (libsource (lib "SCH_XIJUN") (part "RES_1K  5% 0603"))
    )
    (comp (ref "RE1")
      (value "12K 5%")
      (footprint "0805")
      (description "RS-05K-512±5%(5.1KΩ 5%)")
      (fields (field (name "Comment") "电阻(贴片)"))
      (libsource (lib "SCH_XIJUN") (part "RES_5.1K 5% 0805"))
    )
    (comp (ref "RE2")
      (value "12K 5%")
      (footprint "0805")
      (description "RS-05K-512±5%(5.1KΩ 5%)")
      (fields (field (name "Comment") "电阻(贴片)"))
      (libsource (lib "SCH_XIJUN") (part "RES_5.1K 5% 0805"))
    )
    (comp (ref "RE3")
      (value "12K 5%")
      (footprint "0805")
      (description "RS-05K-512±5%(5.1KΩ 5%)")
      (fields (field (name "Comment") "电阻(贴片)"))
      (libsource (lib "SCH_XIJUN") (part "RES_5.1K 5% 0805"))
    )
    (comp (ref "RE4")
      (value "12K 5%")
      (footprint "0805")
      (description "RS-05K-512±5%(5.1KΩ 5%)")
      (fields (field (name "Comment") "电阻(贴片)"))
      (libsource (lib "SCH_XIJUN") (part "RES_5.1K 5% 0805"))
    )
    (comp (ref "RE5")
      (value "12K 5%")
      (footprint "0805")
      (description "RS-05K-512±5%(5.1KΩ 5%)")
      (fields (field (name "Comment") "电阻(贴片)"))
      (libsource (lib "SCH_XIJUN") (part "RES_5.1K 5% 0805"))
    )
    (comp (ref "RE6")
      (value "12K 5%")
      (footprint "0805")
      (description "RS-05K-512±5%(5.1KΩ 5%)")
      (fields (field (name "Comment") "电阻(贴片)"))
      (libsource (lib "SCH_XIJUN") (part "RES_5.1K 5% 0805"))
    )
    (comp (ref "RE7")
      (value "12K 5%")
      (footprint "0805")
      (description "RS-05K-512±5%(5.1KΩ 5%)")
      (fields (field (name "Comment") "电阻(贴片)"))
      (libsource (lib "SCH_XIJUN") (part "RES_5.1K 5% 0805"))
    )
    (comp (ref "RE8")
      (value "12K 5%")
      (footprint "0805")
      (description "RS-05K-512±5%(5.1KΩ 5%)")
      (fields (field (name "Comment") "电阻(贴片)"))
      (libsource (lib "SCH_XIJUN") (part "RES_5.1K 5% 0805"))
    )
    (comp (ref "RE9")
      (value "12K 5%")
      (footprint "0805")
      (description "RS-05K-512±5%(5.1KΩ 5%)")
      (fields (field (name "Comment") "电阻(贴片)"))
      (libsource (lib "SCH_XIJUN") (part "RES_5.1K 5% 0805"))
    )
    (comp (ref "RE10")
      (value "12K 5%")
      (footprint "0805")
      (description "RS-05K-512±5%(5.1KΩ 5%)")
      (fields (field (name "Comment") "电阻(贴片)"))
      (libsource (lib "SCH_XIJUN") (part "RES_5.1K 5% 0805"))
    )
    (comp (ref "RE11")
      (value "12K 5%")
      (footprint "0805")
      (description "RS-05K-512±5%(5.1KΩ 5%)")
      (fields (field (name "Comment") "电阻(贴片)"))
      (libsource (lib "SCH_XIJUN") (part "RES_5.1K 5% 0805"))
    )
    (comp (ref "RE12")
      (value "12K 5%")
      (footprint "0805")
      (description "RS-05K-512±5%(5.1KΩ 5%)")
      (fields (field (name "Comment") "电阻(贴片)"))
      (libsource (lib "SCH_XIJUN") (part "RES_5.1K 5% 0805"))
    )
    (comp (ref "RE13")
      (value "12K 5%")
      (footprint "0805")
      (description "RS-05K-123±5%(12KΩ 5%)")
      (fields (field (name "Comment") "电阻(贴片)"))
      (libsource (lib "SCH_XIJUN") (part "RES_5.1K 5% 0805"))
    )
    (comp (ref "RE14")
      (value "12K 5%")
      (footprint "0805")
      (description "RS-05K-512±5%(5.1KΩ 5%)")
      (fields (field (name "Comment") "电阻(贴片)"))
      (libsource (lib "SCH_XIJUN") (part "RES_5.1K 5% 0805"))
    )
    (comp (ref "RE15")
      (value "12K 5%")
      (footprint "0805")
      (description "RS-05K-512±5%(5.1KΩ 5%)")
      (fields (field (name "Comment") "电阻(贴片)"))
      (libsource (lib "SCH_XIJUN") (part "RES_5.1K 5% 0805"))
    )
    (comp (ref "RE16")
      (value "12K 5%")
      (footprint "0805")
      (description "RS-05K-512±5%(5.1KΩ 5%)")
      (fields (field (name "Comment") "电阻(贴片)"))
      (libsource (lib "SCH_XIJUN") (part "RES_5.1K 5% 0805"))
    )
    (comp (ref "RH1")
      (value "510Ω 5%")
      (footprint "0805")
      (description "RS-05K-511±5%(510Ω)")
      (fields (field (name "Comment") "电阻(贴片)"))
      (libsource (lib "SCH_XIJUN") (part "RES_200Ω5% 0805"))
    )
    (comp (ref "RH2")
      (value "510Ω 5%")
      (footprint "0805")
      (description "RS-05K-511±5%(510Ω)")
      (fields (field (name "Comment") "电阻(贴片)"))
      (libsource (lib "SCH_XIJUN") (part "RES_200Ω5% 0805"))
    )
    (comp (ref "RH3")
      (value "2K 5%")
      (footprint "0805")
      (description "RS-05K-2K±5%(2K)")
      (fields (field (name "Comment") "电阻(贴片)"))
      (libsource (lib "SCH_XIJUN") (part "RES_4.7KΩ5% 0805"))
    )
    (comp (ref "RH4")
      (value "510Ω 5%")
      (footprint "0805")
      (description "RS-05K-511±5%(510Ω)")
      (fields (field (name "Comment") "电阻(贴片)"))
      (libsource (lib "SCH_XIJUN") (part "RES_200Ω5% 0805"))
    )
    (comp (ref "RH5")
      (value "510Ω 5%")
      (footprint "0805")
      (description "RS-05K-511±5%(510Ω)")
      (fields (field (name "Comment") "电阻(贴片)"))
      (libsource (lib "SCH_XIJUN") (part "RES_200Ω5% 0805"))
    )
    (comp (ref "RH6")
      (value "2K 5%")
      (footprint "0805")
      (description "RS-05K-2K±5%(2K)")
      (fields (field (name "Comment") "电阻(贴片)"))
      (libsource (lib "SCH_XIJUN") (part "RES_4.7KΩ5% 0805"))
    )
    (comp (ref "RH7")
      (value "510Ω 5%")
      (footprint "0805")
      (description "RS-05K-511±5%(510Ω)")
      (fields (field (name "Comment") "电阻(贴片)"))
      (libsource (lib "SCH_XIJUN") (part "RES_200Ω5% 0805"))
    )
    (comp (ref "RH8")
      (value "510Ω 5%")
      (footprint "0805")
      (description "RS-05K-511±5%(510Ω)")
      (fields (field (name "Comment") "电阻(贴片)"))
      (libsource (lib "SCH_XIJUN") (part "RES_200Ω5% 0805"))
    )
    (comp (ref "RH9")
      (value "2K 5%")
      (footprint "0805")
      (description "RS-05K-2K±5%(2K)")
      (fields (field (name "Comment") "电阻(贴片)"))
      (libsource (lib "SCH_XIJUN") (part "RES_4.7KΩ5% 0805"))
    )
    (comp (ref "RH10")
      (value "510Ω 5%")
      (footprint "0805")
      (description "RS-05K-511±5%(510Ω)")
      (fields (field (name "Comment") "电阻(贴片)"))
      (libsource (lib "SCH_XIJUN") (part "RES_200Ω5% 0805"))
    )
    (comp (ref "RH11")
      (value "510Ω 5%")
      (footprint "0805")
      (description "RS-05K-511±5%(510Ω)")
      (fields (field (name "Comment") "电阻(贴片)"))
      (libsource (lib "SCH_XIJUN") (part "RES_200Ω5% 0805"))
    )
    (comp (ref "RH12")
      (value "2K 5%")
      (footprint "0805")
      (description "RS-05K-2K±5%(2K)")
      (fields (field (name "Comment") "电阻(贴片)"))
      (libsource (lib "SCH_XIJUN") (part "RES_4.7KΩ5% 0805"))
    )
    (comp (ref "RH13")
      (value "2K 5%")
      (footprint "0805")
      (description "RS-05K-2K±5%(2K)")
      (fields (field (name "Comment") "电阻(贴片)"))
      (libsource (lib "SCH_XIJUN") (part "RES_4.7KΩ5% 0805"))
    )
    (comp (ref "RH14")
      (value "510Ω 5%")
      (footprint "0805")
      (description "RS-05K-511±5%(510Ω)")
      (fields (field (name "Comment") "电阻(贴片)"))
      (libsource (lib "SCH_XIJUN") (part "RES_200Ω5% 0805"))
    )
    (comp (ref "RH15")
      (value "510Ω 5%")
      (footprint "0805")
      (description "RS-05K-511±5%(510Ω)")
      (fields (field (name "Comment") "电阻(贴片)"))
      (libsource (lib "SCH_XIJUN") (part "RES_200Ω5% 0805"))
    )
    (comp (ref "RH16")
      (value "2K 5%")
      (footprint "0805")
      (description "RS-05K-2K±5%(2K)")
      (fields (field (name "Comment") "电阻(贴片)"))
      (libsource (lib "SCH_XIJUN") (part "RES_4.7KΩ5% 0805"))
    )
    (comp (ref "RH17")
      (value "510Ω 5%")
      (footprint "0805")
      (description "RS-05K-511±5%(510Ω)")
      (fields (field (name "Comment") "电阻(贴片)"))
      (libsource (lib "SCH_XIJUN") (part "RES_200Ω5% 0805"))
    )
    (comp (ref "RH18")
      (value "510Ω 5%")
      (footprint "0805")
      (description "RS-05K-511±5%(510Ω)")
      (fields (field (name "Comment") "电阻(贴片)"))
      (libsource (lib "SCH_XIJUN") (part "RES_200Ω5% 0805"))
    )
    (comp (ref "RH19")
      (value "2K 5%")
      (footprint "0805")
      (description "RS-05K-2K±5%(2K)")
      (fields (field (name "Comment") "电阻(贴片)"))
      (libsource (lib "SCH_XIJUN") (part "RES_4.7KΩ5% 0805"))
    )
    (comp (ref "RH20")
      (value "510Ω 5%")
      (footprint "0805")
      (description "RS-05K-511±5%(510Ω)")
      (fields (field (name "Comment") "电阻(贴片)"))
      (libsource (lib "SCH_XIJUN") (part "RES_200Ω5% 0805"))
    )
    (comp (ref "RH21")
      (value "510Ω 5%")
      (footprint "0805")
      (description "RS-05K-511±5%(510Ω)")
      (fields (field (name "Comment") "电阻(贴片)"))
      (libsource (lib "SCH_XIJUN") (part "RES_200Ω5% 0805"))
    )
    (comp (ref "RH22")
      (value "2K 5%")
      (footprint "0805")
      (description "RS-05K-2K±5%(2K)")
      (fields (field (name "Comment") "电阻(贴片)"))
      (libsource (lib "SCH_XIJUN") (part "RES_4.7KΩ5% 0805"))
    )
    (comp (ref "RH23")
      (value "510Ω 5%")
      (footprint "0805")
      (description "RS-05K-511±5%(510Ω)")
      (fields (field (name "Comment") "电阻(贴片)"))
      (libsource (lib "SCH_XIJUN") (part "RES_200Ω5% 0805"))
    )
    (comp (ref "RH24")
      (value "510Ω 5%")
      (footprint "0805")
      (description "RS-05K-511±5%(510Ω)")
      (fields (field (name "Comment") "电阻(贴片)"))
      (libsource (lib "SCH_XIJUN") (part "RES_200Ω5% 0805"))
    )
    (comp (ref "TL1")
      (value "TLP281")
      (footprint "SOP16")
      (description "TLP281-4/SOP16")
      (fields (field (name "Comment") "光耦(贴片)"))
      (libsource (lib "SCH_XIJUN") (part "隔离光耦 TLP281-4/SOP16"))
    )
    (comp (ref "TL2")
      (value "TLP281")
      (footprint "SOP16")
      (description "TLP281-4/SOP16")
      (fields (field (name "Comment") "光耦(贴片)"))
      (libsource (lib "SCH_XIJUN") (part "隔离光耦 TLP281-4/SOP16"))
    )
    (comp (ref "TL3")
      (value "TLP281")
      (footprint "SOP16")
      (description "TLP281-4/SOP16")
      (fields (field (name "Comment") "光耦(贴片)"))
      (libsource (lib "SCH_XIJUN") (part "隔离光耦 TLP281-4/SOP16"))
    )
    (comp (ref "TL4")
      (value "TLP281")
      (footprint "SOP16")
      (description "TLP281-4/SOP16")
      (fields (field (name "Comment") "光耦(贴片)"))
      (libsource (lib "SCH_XIJUN") (part "隔离光耦 TLP281-4/SOP16"))
    )
    (comp (ref "TL5")
      (value "TLP281")
      (footprint "SOP16")
      (description "TLP281-4/SOP16")
      (fields (field (name "Comment") "光耦(贴片)"))
      (libsource (lib "SCH_XIJUN") (part "隔离光耦 TLP281-4/SOP16"))
    )
    (comp (ref "TL6")
      (value "TLP281")
      (footprint "SOP16")
      (description "TLP281-4/SOP16")
      (fields (field (name "Comment") "光耦(贴片)"))
      (libsource (lib "SCH_XIJUN") (part "隔离光耦 TLP281-4/SOP16"))
    )
    (comp (ref "U1")
      (value "集成电路")
      (footprint "sop8")
      (description "TJA1050")
      (libsource (lib "MYlib") (part "TJA1050"))
    )
    (comp (ref "U2")
      (value "LM2596S-5.0")
      (footprint "TO-263")
      (description "SIMPLE SWITCHER 1A STEP DOWN VOLTAGE REGULATOR")
      (libsource (lib "*") (part "LM2575T5.0(5)"))
    )
    (comp (ref "U4")
      (value "DM9000")
      (footprint "mTQFP48")
      (libsource (lib "WarShip V3 STM32103封装库") (part "DM9000A"))
    )
    (comp (ref "U5")
      (value "集成电路")
      (footprint "sop8")
      (description "SP485")
      (libsource (lib "MYlib") (part "SP485"))
    )
    (comp (ref "U6")
      (value "AMS1117-3.3")
      (footprint "AMS1117")
      (libsource (lib "WarShip V3 STM32103封装库") (part "AMS1117"))
    )
    (comp (ref "V1")
      (value "SK210B")
      (footprint "1812DT")
      (description "1N5824")
      (libsource (lib "SCH") (part "DIODE1"))
    )
    (comp (ref "Y1")
      (value "25M")
      (footprint "CRYSTAL_SMD")
      (description "HC-49SMD/25.000MHz")
      (fields (field (name "Comment") "晶体(贴片)") (field (name "PUBLISHER") "Altium Limited"))
      (libsource (lib "altium-import") (part "root_0_CRYSTAL 12M HC-49SMD_"))
    )
  )
  (nets
    (net (code "1") (name "/485_A") (class "Default")
      (node (ref "D1") (pin "1") (pinfunction "1_1") (pintype "passive"))
      (node (ref "P8") (pin "1") (pinfunction "1_1") (pintype "passive"))
      (node (ref "R28") (pin "1") (pinfunction "1_1") (pintype "passive"))
      (node (ref "R30") (pin "1") (pinfunction "1_1") (pintype "passive"))
      (node (ref "U5") (pin "6") (pinfunction "A_6") (pintype "passive"))
    )
    (net (code "2") (name "/485_B") (class "Default")
      (node (ref "D1") (pin "2") (pinfunction "2_2") (pintype "passive"))
      (node (ref "P8") (pin "2") (pinfunction "2_2") (pintype "passive"))
      (node (ref "R30") (pin "2") (pinfunction "2_2") (pintype "passive"))
      (node (ref "R38") (pin "1") (pinfunction "1_1") (pintype "passive"))
      (node (ref "U5") (pin "7") (pinfunction "B_7") (pintype "passive"))
    )
    (net (code "3") (name "/A0") (class "Default")
      (node (ref "P4") (pin "1") (pinfunction "1_1") (pintype "passive"))
      (node (ref "P6") (pin "2") (pinfunction "2_2") (pintype "passive"))
    )
    (net (code "4") (name "/A1") (class "Default")
      (node (ref "P4") (pin "3") (pinfunction "3_3") (pintype "passive"))
      (node (ref "P6") (pin "3") (pinfunction "3_3") (pintype "passive"))
    )
    (net (code "5") (name "/A2") (class "Default")
      (node (ref "P4") (pin "5") (pinfunction "5_5") (pintype "passive"))
      (node (ref "P6") (pin "4") (pinfunction "4_4") (pintype "passive"))
    )
    (net (code "6") (name "/CAN_RX") (class "Default")
      (node (ref "P7") (pin "4") (pinfunction "4_4") (pintype "passive"))
      (node (ref "U1") (pin "4") (pinfunction "RXD_4") (pintype "passive"))
    )
    (net (code "7") (name "/CAN_TX") (class "Default")
      (node (ref "P7") (pin "3") (pinfunction "3_3") (pintype "passive"))
      (node (ref "U1") (pin "1") (pinfunction "TXD_1") (pintype "passive"))
    )
    (net (code "8") (name "/CH0") (class "Default")
      (node (ref "P4") (pin "2") (pinfunction "2_2") (pintype "passive"))
      (node (ref "P6") (pin "27") (pinfunction "27_27") (pintype "passive"))
    )
    (net (code "9") (name "/CH1") (class "Default")
      (node (ref "P4") (pin "4") (pinfunction "4_4") (pintype "passive"))
      (node (ref "P6") (pin "28") (pinfunction "28_28") (pintype "passive"))
    )
    (net (code "10") (name "/CH2") (class "Default")
      (node (ref "P4") (pin "6") (pinfunction "6_6") (pintype "passive"))
      (node (ref "P6") (pin "29") (pinfunction "29_29") (pintype "passive"))
    )
    (net (code "11") (name "/CH3") (class "Default")
      (node (ref "P4") (pin "8") (pinfunction "8_8") (pintype "passive"))
      (node (ref "P6") (pin "30") (pinfunction "30_30") (pintype "passive"))
    )
    (net (code "12") (name "/CH4") (class "Default")
      (node (ref "P4") (pin "10") (pinfunction "10_10") (pintype "passive"))
      (node (ref "P6") (pin "35") (pinfunction "35_35") (pintype "passive"))
    )
    (net (code "13") (name "/CH5") (class "Default")
      (node (ref "P4") (pin "12") (pinfunction "12_12") (pintype "passive"))
      (node (ref "P6") (pin "36") (pinfunction "36_36") (pintype "passive"))
    )
    (net (code "14") (name "/CH6") (class "Default")
      (node (ref "P4") (pin "14") (pinfunction "14_14") (pintype "passive"))
      (node (ref "P6") (pin "33") (pinfunction "33_33") (pintype "passive"))
    )
    (net (code "15") (name "/CH7") (class "Default")
      (node (ref "P4") (pin "16") (pinfunction "16_16") (pintype "passive"))
      (node (ref "P6") (pin "34") (pinfunction "34_34") (pintype "passive"))
    )
    (net (code "16") (name "/CH8") (class "Default")
      (node (ref "P4") (pin "18") (pinfunction "18_18") (pintype "passive"))
      (node (ref "P6") (pin "37") (pinfunction "37_37") (pintype "passive"))
    )
    (net (code "17") (name "/CH9") (class "Default")
      (node (ref "P4") (pin "20") (pinfunction "20_20") (pintype "passive"))
      (node (ref "P6") (pin "38") (pinfunction "38_38") (pintype "passive"))
    )
    (net (code "18") (name "/CH10") (class "Default")
      (node (ref "P4") (pin "22") (pinfunction "22_22") (pintype "passive"))
      (node (ref "P6") (pin "21") (pinfunction "21_21") (pintype "passive"))
    )
    (net (code "19") (name "/CH11") (class "Default")
      (node (ref "P4") (pin "24") (pinfunction "24_24") (pintype "passive"))
      (node (ref "P6") (pin "22") (pinfunction "22_22") (pintype "passive"))
    )
    (net (code "20") (name "/CH12") (class "Default")
      (node (ref "P6") (pin "23") (pinfunction "23_23") (pintype "passive"))
    )
    (net (code "21") (name "/CH13") (class "Default")
      (node (ref "P6") (pin "24") (pinfunction "24_24") (pintype "passive"))
    )
    (net (code "22") (name "/DAC_OUT1") (class "Default")
      (node (ref "P6") (pin "31") (pinfunction "31_31") (pintype "passive"))
    )
    (net (code "23") (name "/DAC_OUT2") (class "Default")
      (node (ref "P6") (pin "32") (pinfunction "32_32") (pintype "passive"))
    )
    (net (code "24") (name "/DM9000_INT") (class "Default")
      (node (ref "D3") (pin "1") (pinfunction "A_1") (pintype "passive"))
      (node (ref "P7") (pin "44") (pinfunction "44_44") (pintype "passive"))
    )
    (net (code "25") (name "/DM9000_RST") (class "Default")
      (node (ref "P7") (pin "21") (pinfunction "21_21") (pintype "passive"))
      (node (ref "R33") (pin "1") (pinfunction "1_1") (pintype "passive"))
      (node (ref "U4") (pin "40") (pinfunction "PWRST_40") (pintype "passive"))
    )
    (net (code "26") (name "/EN") (class "Default")
      (node (ref "P4") (pin "7") (pinfunction "7_7") (pintype "passive"))
      (node (ref "P6") (pin "5") (pinfunction "5_5") (pintype "passive"))
    )
    (net (code "27") (name "/EXT_IN_CH0") (class "Default")
      (node (ref "P1") (pin "8") (pinfunction "8_8") (pintype "passive"))
      (node (ref "RH22") (pin "2") (pinfunction "2_2") (pintype "passive"))
    )
    (net (code "28") (name "/EXT_IN_CH1") (class "Default")
      (node (ref "P1") (pin "7") (pinfunction "7_7") (pintype "passive"))
      (node (ref "RH19") (pin "2") (pinfunction "2_2") (pintype "passive"))
    )
    (net (code "29") (name "/EXT_IN_CH2") (class "Default")
      (node (ref "P1") (pin "6") (pinfunction "6_6") (pintype "passive"))
      (node (ref "RH16") (pin "2") (pinfunction "2_2") (pintype "passive"))
    )
    (net (code "30") (name "/EXT_IN_CH3") (class "Default")
      (node (ref "P1") (pin "5") (pinfunction "5_5") (pintype "passive"))
      (node (ref "RH13") (pin "2") (pinfunction "2_2") (pintype "passive"))
    )
    (net (code "31") (name "/EXT_IN_CH4") (class "Default")
      (node (ref "P1") (pin "4") (pinfunction "4_4") (pintype "passive"))
      (node (ref "RH12") (pin "2") (pinfunction "2_2") (pintype "passive"))
    )
    (net (code "32") (name "/EXT_IN_CH5") (class "Default")
      (node (ref "P1") (pin "3") (pinfunction "3_3") (pintype "passive"))
      (node (ref "RH9") (pin "2") (pinfunction "2_2") (pintype "passive"))
    )
    (net (code "33") (name "/EXT_IN_CH6") (class "Default")
      (node (ref "P1") (pin "2") (pinfunction "2_2") (pintype "passive"))
      (node (ref "RH6") (pin "2") (pinfunction "2_2") (pintype "passive"))
    )
    (net (code "34") (name "/EXT_IN_CH7") (class "Default")
      (node (ref "P1") (pin "1") (pinfunction "1_1") (pintype "passive"))
      (node (ref "RH3") (pin "2") (pinfunction "2_2") (pintype "passive"))
    )
    (net (code "35") (name "/EXT_OUT_CH0") (class "Default")
      (node (ref "DE1") (pin "2") (pinfunction "K_2") (pintype "passive"))
      (node (ref "P2") (pin "16") (pinfunction "16_16") (pintype "passive"))
      (node (ref "QE1") (pin "2") (pinfunction "2_2") (pintype "passive"))
      (node (ref "RE1") (pin "1") (pinfunction "1_1") (pintype "passive"))
    )
    (net (code "36") (name "/EXT_OUT_CH1") (class "Default")
      (node (ref "DE2") (pin "2") (pinfunction "K_2") (pintype "passive"))
      (node (ref "P2") (pin "15") (pinfunction "15_15") (pintype "passive"))
      (node (ref "QE2") (pin "2") (pinfunction "2_2") (pintype "passive"))
      (node (ref "RE2") (pin "1") (pinfunction "1_1") (pintype "passive"))
    )
    (net (code "37") (name "/EXT_OUT_CH2") (class "Default")
      (node (ref "DE3") (pin "2") (pinfunction "K_2") (pintype "passive"))
      (node (ref "P2") (pin "14") (pinfunction "14_14") (pintype "passive"))
      (node (ref "QE3") (pin "2") (pinfunction "2_2") (pintype "passive"))
      (node (ref "RE3") (pin "1") (pinfunction "1_1") (pintype "passive"))
    )
    (net (code "38") (name "/EXT_OUT_CH3") (class "Default")
      (node (ref "DE4") (pin "2") (pinfunction "K_2") (pintype "passive"))
      (node (ref "P2") (pin "13") (pinfunction "13_13") (pintype "passive"))
      (node (ref "QE4") (pin "2") (pinfunction "2_2") (pintype "passive"))
      (node (ref "RE4") (pin "1") (pinfunction "1_1") (pintype "passive"))
    )
    (net (code "39") (name "/EXT_OUT_CH4") (class "Default")
      (node (ref "DE5") (pin "2") (pinfunction "K_2") (pintype "passive"))
      (node (ref "P2") (pin "12") (pinfunction "12_12") (pintype "passive"))
      (node (ref "QE5") (pin "2") (pinfunction "2_2") (pintype "passive"))
      (node (ref "RE5") (pin "1") (pinfunction "1_1") (pintype "passive"))
    )
    (net (code "40") (name "/EXT_OUT_CH5") (class "Default")
      (node (ref "DE6") (pin "2") (pinfunction "K_2") (pintype "passive"))
      (node (ref "P2") (pin "11") (pinfunction "11_11") (pintype "passive"))
      (node (ref "QE6") (pin "2") (pinfunction "2_2") (pintype "passive"))
      (node (ref "RE6") (pin "1") (pinfunction "1_1") (pintype "passive"))
    )
    (net (code "41") (name "/EXT_OUT_CH6") (class "Default")
      (node (ref "DE7") (pin "2") (pinfunction "K_2") (pintype "passive"))
      (node (ref "P2") (pin "10") (pinfunction "10_10") (pintype "passive"))
      (node (ref "QE7") (pin "2") (pinfunction "2_2") (pintype "passive"))
      (node (ref "RE7") (pin "1") (pinfunction "1_1") (pintype "passive"))
    )
    (net (code "42") (name "/EXT_OUT_CH7") (class "Default")
      (node (ref "DE8") (pin "2") (pinfunction "K_2") (pintype "passive"))
      (node (ref "P2") (pin "9") (pinfunction "9_9") (pintype "passive"))
      (node (ref "QE8") (pin "2") (pinfunction "2_2") (pintype "passive"))
      (node (ref "RE8") (pin "1") (pinfunction "1_1") (pintype "passive"))
    )
    (net (code "43") (name "/EXT_OUT_CH8") (class "Default")
      (node (ref "DE9") (pin "2") (pinfunction "K_2") (pintype "passive"))
      (node (ref "P2") (pin "8") (pinfunction "8_8") (pintype "passive"))
      (node (ref "QE9") (pin "2") (pinfunction "2_2") (pintype "passive"))
      (node (ref "RE9") (pin "1") (pinfunction "1_1") (pintype "passive"))
    )
    (net (code "44") (name "/EXT_OUT_CH9") (class "Default")
      (node (ref "DE10") (pin "2") (pinfunction "K_2") (pintype "passive"))
      (node (ref "P2") (pin "7") (pinfunction "7_7") (pintype "passive"))
      (node (ref "QE10") (pin "2") (pinfunction "2_2") (pintype "passive"))
      (node (ref "RE10") (pin "1") (pinfunction "1_1") (pintype "passive"))
    )
    (net (code "45") (name "/EXT_OUT_CH10") (class "Default")
      (node (ref "DE11") (pin "2") (pinfunction "K_2") (pintype "passive"))
      (node (ref "P2") (pin "6") (pinfunction "6_6") (pintype "passive"))
      (node (ref "QE11") (pin "2") (pinfunction "2_2") (pintype "passive"))
      (node (ref "RE11") (pin "1") (pinfunction "1_1") (pintype "passive"))
    )
    (net (code "46") (name "/EXT_OUT_CH11") (class "Default")
      (node (ref "DE12") (pin "2") (pinfunction "K_2") (pintype "passive"))
      (node (ref "P2") (pin "5") (pinfunction "5_5") (pintype "passive"))
      (node (ref "QE12") (pin "2") (pinfunction "2_2") (pintype "passive"))
      (node (ref "RE12") (pin "1") (pinfunction "1_1") (pintype "passive"))
    )
    (net (code "47") (name "/EXT_OUT_CH12") (class "Default")
      (node (ref "DE13") (pin "2") (pinfunction "K_2") (pintype "passive"))
      (node (ref "P2") (pin "4") (pinfunction "4_4") (pintype "passive"))
      (node (ref "QE13") (pin "2") (pinfunction "2_2") (pintype "passive"))
      (node (ref "RE13") (pin "1") (pinfunction "1_1") (pintype "passive"))
    )
    (net (code "48") (name "/EXT_OUT_CH13") (class "Default")
      (node (ref "DE14") (pin "2") (pinfunction "K_2") (pintype "passive"))
      (node (ref "P2") (pin "3") (pinfunction "3_3") (pintype "passive"))
      (node (ref "QE14") (pin "2") (pinfunction "2_2") (pintype "passive"))
      (node (ref "RE14") (pin "1") (pinfunction "1_1") (pintype "passive"))
    )
    (net (code "49") (name "/EXT_OUT_CH14") (class "Default")
      (node (ref "DE15") (pin "2") (pinfunction "K_2") (pintype "passive"))
      (node (ref "P2") (pin "2") (pinfunction "2_2") (pintype "passive"))
      (node (ref "QE15") (pin "2") (pinfunction "2_2") (pintype "passive"))
      (node (ref "RE15") (pin "1") (pinfunction "1_1") (pintype "passive"))
    )
    (net (code "50") (name "/EXT_OUT_CH15") (class "Default")
      (node (ref "DE16") (pin "2") (pinfunction "K_2") (pintype "passive"))
      (node (ref "P2") (pin "1") (pinfunction "1_1") (pintype "passive"))
      (node (ref "QE16") (pin "2") (pinfunction "2_2") (pintype "passive"))
      (node (ref "RE16") (pin "1") (pinfunction "1_1") (pintype "passive"))
    )
    (net (code "51") (name "/FSMC_A0") (class "Default")
      (node (ref "P6") (pin "7") (pinfunction "7_7") (pintype "passive"))
      (node (ref "RH1") (pin "2") (pinfunction "2_2") (pintype "passive"))
    )
    (net (code "52") (name "/FSMC_A1") (class "Default")
      (node (ref "P6") (pin "8") (pinfunction "8_8") (pintype "passive"))
      (node (ref "RH4") (pin "2") (pinfunction "2_2") (pintype "passive"))
    )
    (net (code "53") (name "/FSMC_A2") (class "Default")
      (node (ref "P6") (pin "9") (pinfunction "9_9") (pintype "passive"))
      (node (ref "RH7") (pin "2") (pinfunction "2_2") (pintype "passive"))
    )
    (net (code "54") (name "/FSMC_A3") (class "Default")
      (node (ref "P6") (pin "10") (pinfunction "10_10") (pintype "passive"))
      (node (ref "RH10") (pin "2") (pinfunction "2_2") (pintype "passive"))
    )
    (net (code "55") (name "/FSMC_A4") (class "Default")
      (node (ref "P6") (pin "11") (pinfunction "11_11") (pintype "passive"))
      (node (ref "RH14") (pin "2") (pinfunction "2_2") (pintype "passive"))
    )
    (net (code "56") (name "/FSMC_A5") (class "Default")
      (node (ref "P6") (pin "12") (pinfunction "12_12") (pintype "passive"))
      (node (ref "RH17") (pin "2") (pinfunction "2_2") (pintype "passive"))
    )
    (net (code "57") (name "/FSMC_A6") (class "Default")
      (node (ref "P6") (pin "40") (pinfunction "40_40") (pintype "passive"))
      (node (ref "RH15") (pin "2") (pinfunction "2_2") (pintype "passive"))
    )
    (net (code "58") (name "/FSMC_A7") (class "Default")
      (node (ref "P6") (pin "41") (pinfunction "41_41") (pintype "passive"))
      (node (ref "RH18") (pin "2") (pinfunction "2_2") (pintype "passive"))
      (node (ref "U4") (pin "32") (pinfunction "CMD_32") (pintype "passive"))
    )
    (net (code "59") (name "/FSMC_A8") (class "Default")
      (node (ref "P6") (pin "42") (pinfunction "42_42") (pintype "passive"))
      (node (ref "RH21") (pin "2") (pinfunction "2_2") (pintype "passive"))
    )
    (net (code "60") (name "/FSMC_A9") (class "Default")
      (node (ref "P6") (pin "43") (pinfunction "43_43") (pintype "passive"))
      (node (ref "RH24") (pin "2") (pinfunction "2_2") (pintype "passive"))
    )
    (net (code "61") (name "/FSMC_A10") (class "Default")
      (node (ref "P6") (pin "44") (pinfunction "44_44") (pintype "passive"))
      (node (ref "R50") (pin "1") (pinfunction "1_1") (pintype "passive"))
    )
    (net (code "62") (name "/FSMC_A11") (class "Default")
      (node (ref "P6") (pin "45") (pinfunction "45_45") (pintype "passive"))
      (node (ref "R51") (pin "1") (pinfunction "1_1") (pintype "passive"))
    )
    (net (code "63") (name "/FSMC_A12") (class "Default")
      (node (ref "P7") (pin "48") (pinfunction "48_48") (pintype "passive"))
      (node (ref "R52") (pin "1") (pinfunction "1_1") (pintype "passive"))
    )
    (net (code "64") (name "/FSMC_A13") (class "Default")
      (node (ref "P7") (pin "47") (pinfunction "47_47") (pintype "passive"))
      (node (ref "R53") (pin "1") (pinfunction "1_1") (pintype "passive"))
    )
    (net (code "65") (name "/FSMC_A14") (class "Default")
      (node (ref "P7") (pin "46") (pinfunction "46_46") (pintype "passive"))
    )
    (net (code "66") (name "/FSMC_A15") (class "Default")
      (node (ref "P7") (pin "45") (pinfunction "45_45") (pintype "passive"))
    )
    (net (code "67") (name "/FSMC_A16") (class "Default")
      (node (ref "P7") (pin "53") (pinfunction "53_53") (pintype "passive"))
    )
    (net (code "68") (name "/FSMC_A17") (class "Default")
      (node (ref "P7") (pin "52") (pinfunction "52_52") (pintype "passive"))
    )
    (net (code "69") (name "/FSMC_A18") (class "Default")
      (node (ref "P7") (pin "51") (pinfunction "51_51") (pintype "passive"))
    )
    (net (code "70") (name "/FSMC_A23") (class "Default")
      (node (ref "P6") (pin "1") (pinfunction "1_1") (pintype "passive"))
    )
    (net (code "71") (name "/FSMC_A24") (class "Default")
      (node (ref "P7") (pin "16") (pinfunction "16_16") (pintype "passive"))
    )
    (net (code "72") (name "/FSMC_A25") (class "Default")
      (node (ref "P7") (pin "15") (pinfunction "15_15") (pintype "passive"))
    )
    (net (code "73") (name "/FSMC_CD") (class "Default")
      (node (ref "P6") (pin "18") (pinfunction "18_18") (pintype "passive"))
      (node (ref "RH5") (pin "2") (pinfunction "2_2") (pintype "passive"))
    )
    (net (code "74") (name "/FSMC_CLK") (class "Default")
      (node (ref "P7") (pin "27") (pinfunction "27_27") (pintype "passive"))
    )
    (net (code "75") (name "/FSMC_D0") (class "Default")
      (node (ref "P7") (pin "50") (pinfunction "50_50") (pintype "passive"))
      (node (ref "U4") (pin "18") (pinfunction "SD0_18") (pintype "passive"))
    )
    (net (code "76") (name "/FSMC_D1") (class "Default")
      (node (ref "P7") (pin "49") (pinfunction "49_49") (pintype "passive"))
      (node (ref "U4") (pin "17") (pinfunction "SD1_17") (pintype "passive"))
    )
    (net (code "77") (name "/FSMC_D2") (class "Default")
      (node (ref "P7") (pin "30") (pinfunction "30_30") (pintype "passive"))
      (node (ref "U4") (pin "16") (pinfunction "SD2_16") (pintype "passive"))
    )
    (net (code "78") (name "/FSMC_D3") (class "Default")
      (node (ref "P7") (pin "29") (pinfunction "29_29") (pintype "passive"))
      (node (ref "U4") (pin "14") (pinfunction "SD3_14") (pintype "passive"))
    )
    (net (code "79") (name "/FSMC_D4") (class "Default")
      (node (ref "P6") (pin "46") (pinfunction "46_46") (pintype "passive"))
      (node (ref "U4") (pin "13") (pinfunction "SD4_13") (pintype "passive"))
    )
    (net (code "80") (name "/FSMC_D5") (class "Default")
      (node (ref "P6") (pin "47") (pinfunction "47_47") (pintype "passive"))
      (node (ref "U4") (pin "12") (pinfunction "SD5_12") (pintype "passive"))
    )
    (net (code "81") (name "/FSMC_D6") (class "Default")
      (node (ref "P6") (pin "48") (pinfunction "48_48") (pintype "passive"))
      (node (ref "U4") (pin "11") (pinfunction "SD6_11") (pintype "passive"))
    )
    (net (code "82") (name "/FSMC_D7") (class "Default")
      (node (ref "P6") (pin "49") (pinfunction "49_49") (pintype "passive"))
      (node (ref "U4") (pin "10") (pinfunction "SD7_10") (pintype "passive"))
    )
    (net (code "83") (name "/FSMC_D8") (class "Default")
      (node (ref "P6") (pin "50") (pinfunction "50_50") (pintype "passive"))
      (node (ref "U4") (pin "31") (pinfunction "SD8_31") (pintype "passive"))
    )
    (net (code "84") (name "/FSMC_D9") (class "Default")
      (node (ref "P6") (pin "51") (pinfunction "51_51") (pintype "passive"))
      (node (ref "U4") (pin "29") (pinfunction "SD9_29") (pintype "passive"))
    )
    (net (code "85") (name "/FSMC_D10") (class "Default")
      (node (ref "P6") (pin "52") (pinfunction "52_52") (pintype "passive"))
      (node (ref "U4") (pin "28") (pinfunction "SD10_28") (pintype "passive"))
    )
    (net (code "86") (name "/FSMC_D11") (class "Default")
      (node (ref "P6") (pin "53") (pinfunction "53_53") (pintype "passive"))
      (node (ref "U4") (pin "27") (pinfunction "SD11_27") (pintype "passive"))
    )
    (net (code "87") (name "/FSMC_D12") (class "Default")
      (node (ref "P6") (pin "54") (pinfunction "54_54") (pintype "passive"))
      (node (ref "U4") (pin "26") (pinfunction "SD12_26") (pintype "passive"))
    )
    (net (code "88") (name "/FSMC_D13") (class "Default")
      (node (ref "P7") (pin "56") (pinfunction "56_56") (pintype "passive"))
      (node (ref "U4") (pin "25") (pinfunction "SD13_25") (pintype "passive"))
    )
    (net (code "89") (name "/FSMC_D14") (class "Default")
      (node (ref "P7") (pin "55") (pinfunction "55_55") (pintype "passive"))
      (node (ref "U4") (pin "24") (pinfunction "SD14_24") (pintype "passive"))
    )
    (net (code "90") (name "/FSMC_D15") (class "Default")
      (node (ref "P7") (pin "54") (pinfunction "54_54") (pintype "passive"))
      (node (ref "U4") (pin "22") (pinfunction "SD15_22") (pintype "passive"))
    )
    (net (code "91") (name "/FSMC_INT3") (class "Default")
      (node (ref "P7") (pin "43") (pinfunction "43_43") (pintype "passive"))
    )
    (net (code "92") (name "/FSMC_INTR") (class "Default")
      (node (ref "P6") (pin "19") (pinfunction "19_19") (pintype "passive"))
      (node (ref "RH8") (pin "2") (pinfunction "2_2") (pintype "passive"))
    )
    (net (code "93") (name "/FSMC_NBL0") (class "Default")
      (node (ref "P7") (pin "6") (pinfunction "6_6") (pintype "passive"))
    )
    (net (code "94") (name "/FSMC_NBL1") (class "Default")
      (node (ref "P7") (pin "5") (pinfunction "5_5") (pintype "passive"))
    )
    (net (code "95") (name "/FSMC_NE2") (class "Default")
      (node (ref "P7") (pin "20") (pinfunction "20_20") (pintype "passive"))
      (node (ref "R34") (pin "1") (pinfunction "1_1") (pintype "passive"))
      (node (ref "U4") (pin "37") (pinfunction "CS_37") (pintype "passive"))
    )
    (net (code "96") (name "/FSMC_NE3") (class "Default")
      (node (ref "P7") (pin "19") (pinfunction "19_19") (pintype "passive"))
    )
    (net (code "97") (name "/FSMC_NE4") (class "Default")
      (node (ref "P7") (pin "17") (pinfunction "17_17") (pintype "passive"))
    )
    (net (code "98") (name "/FSMC_NIORD") (class "Default")
      (node (ref "P6") (pin "15") (pinfunction "15_15") (pintype "passive"))
      (node (ref "RH20") (pin "2") (pinfunction "2_2") (pintype "passive"))
    )
    (net (code "99") (name "/FSMC_NIOS16") (class "Default")
      (node (ref "P6") (pin "39") (pinfunction "39_39") (pintype "passive"))
      (node (ref "RH11") (pin "2") (pinfunction "2_2") (pintype "passive"))
    )
    (net (code "100") (name "/FSMC_NIOWR") (class "Default")
      (node (ref "P6") (pin "17") (pinfunction "17_17") (pintype "passive"))
      (node (ref "RH2") (pin "2") (pinfunction "2_2") (pintype "passive"))
    )
    (net (code "101") (name "/FSMC_NOE") (class "Default")
      (node (ref "P7") (pin "26") (pinfunction "26_26") (pintype "passive"))
      (node (ref "U4") (pin "35") (pinfunction "RD_35") (pintype "passive"))
    )
    (net (code "102") (name "/FSMC_NREG") (class "Default")
      (node (ref "P6") (pin "16") (pinfunction "16_16") (pintype "passive"))
      (node (ref "RH23") (pin "2") (pinfunction "2_2") (pintype "passive"))
    )
    (net (code "103") (name "/FSMC_NWAIT") (class "Default")
      (node (ref "P7") (pin "22") (pinfunction "22_22") (pintype "passive"))
      (node (ref "P9") (pin "2") (pinfunction "2_2") (pintype "passive"))
    )
    (net (code "104") (name "/FSMC_NWE") (class "Default")
      (node (ref "P7") (pin "25") (pinfunction "25_25") (pintype "passive"))
      (node (ref "P9") (pin "1") (pinfunction "1_1") (pintype "passive"))
      (node (ref "U4") (pin "36") (pinfunction "WR_36") (pintype "passive"))
    )
    (net (code "105") (name "/I2C1_SCL") (class "Default")
      (node (ref "P7") (pin "10") (pinfunction "10_10") (pintype "passive"))
    )
    (net (code "106") (name "/I2C1_SDA") (class "Default")
      (node (ref "P7") (pin "9") (pinfunction "9_9") (pintype "passive"))
    )
    (net (code "107") (name "/INPUT0") (class "Default")
      (node (ref "R46") (pin "2") (pinfunction "2_2") (pintype "passive"))
      (node (ref "TL6") (pin "16") (pinfunction "C_16") (pintype "passive"))
    )
    (net (code "108") (name "/INPUT1") (class "Default")
      (node (ref "R47") (pin "2") (pinfunction "2_2") (pintype "passive"))
      (node (ref "TL6") (pin "14") (pinfunction "C_14") (pintype "passive"))
    )
    (net (code "109") (name "/INPUT2") (class "Default")
      (node (ref "R48") (pin "2") (pinfunction "2_2") (pintype "passive"))
      (node (ref "TL6") (pin "12") (pinfunction "C_12") (pintype "passive"))
    )
    (net (code "110") (name "/INPUT3") (class "Default")
      (node (ref "R49") (pin "2") (pinfunction "2_2") (pintype "passive"))
      (node (ref "TL6") (pin "10") (pinfunction "C_10") (pintype "passive"))
    )
    (net (code "111") (name "/INPUT4") (class "Default")
      (node (ref "R50") (pin "2") (pinfunction "2_2") (pintype "passive"))
      (node (ref "TL3") (pin "16") (pinfunction "C_16") (pintype "passive"))
    )
    (net (code "112") (name "/INPUT5") (class "Default")
      (node (ref "R51") (pin "2") (pinfunction "2_2") (pintype "passive"))
      (node (ref "TL3") (pin "14") (pinfunction "C_14") (pintype "passive"))
    )
    (net (code "113") (name "/INPUT6") (class "Default")
      (node (ref "R52") (pin "2") (pinfunction "2_2") (pintype "passive"))
      (node (ref "TL3") (pin "12") (pinfunction "C_12") (pintype "passive"))
    )
    (net (code "114") (name "/INPUT7") (class "Default")
      (node (ref "R53") (pin "2") (pinfunction "2_2") (pintype "passive"))
      (node (ref "TL3") (pin "10") (pinfunction "C_10") (pintype "passive"))
    )
    (net (code "115") (name "/LED0") (class "Default")
      (node (ref "P7") (pin "8") (pinfunction "8_8") (pintype "passive"))
    )
    (net (code "116") (name "/LED1") (class "Default")
      (node (ref "P7") (pin "7") (pinfunction "7_7") (pintype "passive"))
    )
    (net (code "117") (name "/LED2") (class "Default")
      (node (ref "P7") (pin "11") (pinfunction "11_11") (pintype "passive"))
    )
    (net (code "118") (name "/LEDA") (class "Default")
      (node (ref "J1") (pin "10") (pinfunction "LED(G)_K_10") (pintype "passive"))
      (node (ref "R41") (pin "2") (pinfunction "2_2") (pintype "passive"))
    )
    (net (code "119") (name "/LEDB") (class "Default")
      (node (ref "J1") (pin "11") (pinfunction "LED(Y)_K_11") (pintype "passive"))
      (node (ref "R40") (pin "2") (pinfunction "2_2") (pintype "passive"))
    )
    (net (code "120") (name "/N24V1") (class "Default")
      (node (ref "P1") (pin "10") (pinfunction "10_10") (pintype "passive"))
      (node (ref "TL3") (pin "2") (pinfunction "K_2") (pintype "passive"))
      (node (ref "TL3") (pin "4") (pinfunction "K_4") (pintype "passive"))
      (node (ref "TL3") (pin "6") (pinfunction "K_6") (pintype "passive"))
      (node (ref "TL3") (pin "8") (pinfunction "K_8") (pintype "passive"))
      (node (ref "TL6") (pin "2") (pinfunction "K_2") (pintype "passive"))
      (node (ref "TL6") (pin "4") (pinfunction "K_4") (pintype "passive"))
      (node (ref "TL6") (pin "6") (pinfunction "K_6") (pintype "passive"))
      (node (ref "TL6") (pin "8") (pinfunction "K_8") (pintype "passive"))
    )
    (net (code "121") (name "/OUT_CH0") (class "Default")
      (node (ref "R1") (pin "1") (pinfunction "1_1") (pintype "passive"))
      (node (ref "TL1") (pin "16") (pinfunction "C_16") (pintype "passive"))
    )
    (net (code "122") (name "/OUT_CH1") (class "Default")
      (node (ref "R2") (pin "1") (pinfunction "1_1") (pintype "passive"))
      (node (ref "TL1") (pin "14") (pinfunction "C_14") (pintype "passive"))
    )
    (net (code "123") (name "/OUT_CH2") (class "Default")
      (node (ref "R3") (pin "1") (pinfunction "1_1") (pintype "passive"))
      (node (ref "TL1") (pin "12") (pinfunction "C_12") (pintype "passive"))
    )
    (net (code "124") (name "/OUT_CH3") (class "Default")
      (node (ref "R4") (pin "1") (pinfunction "1_1") (pintype "passive"))
      (node (ref "TL1") (pin "10") (pinfunction "C_10") (pintype "passive"))
    )
    (net (code "125") (name "/OUT_CH4") (class "Default")
      (node (ref "R5") (pin "1") (pinfunction "1_1") (pintype "passive"))
      (node (ref "TL4") (pin "16") (pinfunction "C_16") (pintype "passive"))
    )
    (net (code "126") (name "/OUT_CH5") (class "Default")
      (node (ref "R6") (pin "1") (pinfunction "1_1") (pintype "passive"))
      (node (ref "TL4") (pin "14") (pinfunction "C_14") (pintype "passive"))
    )
    (net (code "127") (name "/OUT_CH6") (class "Default")
      (node (ref "R7") (pin "1") (pinfunction "1_1") (pintype "passive"))
      (node (ref "TL4") (pin "12") (pinfunction "C_12") (pintype "passive"))
    )
    (net (code "128") (name "/OUT_CH7") (class "Default")
      (node (ref "R8") (pin "1") (pinfunction "1_1") (pintype "passive"))
      (node (ref "TL4") (pin "10") (pinfunction "C_10") (pintype "passive"))
    )
    (net (code "129") (name "/OUT_CH8") (class "Default")
      (node (ref "R9") (pin "1") (pinfunction "1_1") (pintype "passive"))
      (node (ref "TL2") (pin "16") (pinfunction "C_16") (pintype "passive"))
    )
    (net (code "130") (name "/OUT_CH9") (class "Default")
      (node (ref "R10") (pin "1") (pinfunction "1_1") (pintype "passive"))
      (node (ref "TL2") (pin "14") (pinfunction "C_14") (pintype "passive"))
    )
    (net (code "131") (name "/OUT_CH10") (class "Default")
      (node (ref "R11") (pin "1") (pinfunction "1_1") (pintype "passive"))
      (node (ref "TL2") (pin "12") (pinfunction "C_12") (pintype "passive"))
    )
    (net (code "132") (name "/OUT_CH11") (class "Default")
      (node (ref "R12") (pin "1") (pinfunction "1_1") (pintype "passive"))
      (node (ref "TL2") (pin "10") (pinfunction "C_10") (pintype "passive"))
    )
    (net (code "133") (name "/OUT_CH12") (class "Default")
      (node (ref "R13") (pin "1") (pinfunction "1_1") (pintype "passive"))
      (node (ref "TL5") (pin "16") (pinfunction "C_16") (pintype "passive"))
    )
    (net (code "134") (name "/OUT_CH13") (class "Default")
      (node (ref "R14") (pin "1") (pinfunction "1_1") (pintype "passive"))
      (node (ref "TL5") (pin "14") (pinfunction "C_14") (pintype "passive"))
    )
    (net (code "135") (name "/OUT_CH14") (class "Default")
      (node (ref "R15") (pin "1") (pinfunction "1_1") (pintype "passive"))
      (node (ref "TL5") (pin "12") (pinfunction "C_12") (pintype "passive"))
    )
    (net (code "136") (name "/OUT_CH15") (class "Default")
      (node (ref "R16") (pin "1") (pinfunction "1_1") (pintype "passive"))
      (node (ref "TL5") (pin "10") (pinfunction "C_10") (pintype "passive"))
    )
    (net (code "137") (name "/PA8") (class "Default")
      (node (ref "P7") (pin "36") (pinfunction "36_36") (pintype "passive"))
      (node (ref "R48") (pin "1") (pinfunction "1_1") (pintype "passive"))
    )
    (net (code "138") (name "/PB12") (class "Default")
      (node (ref "P7") (pin "60") (pinfunction "60_60") (pintype "passive"))
    )
    (net (code "139") (name "/PB13") (class "Default")
      (node (ref "P7") (pin "59") (pinfunction "59_59") (pintype "passive"))
    )
    (net (code "140") (name "/PB14") (class "Default")
      (node (ref "P7") (pin "58") (pinfunction "58_58") (pintype "passive"))
    )
    (net (code "141") (name "/PB15") (class "Default")
      (node (ref "P7") (pin "57") (pinfunction "57_57") (pintype "passive"))
    )
    (net (code "142") (name "/PC6") (class "Default")
      (node (ref "P7") (pin "40") (pinfunction "40_40") (pintype "passive"))
      (node (ref "R46") (pin "1") (pinfunction "1_1") (pintype "passive"))
    )
    (net (code "143") (name "/PC7") (class "Default")
      (node (ref "P7") (pin "39") (pinfunction "39_39") (pintype "passive"))
      (node (ref "R47") (pin "1") (pinfunction "1_1") (pintype "passive"))
    )
    (net (code "144") (name "/PC13") (class "Default")
      (node (ref "P6") (pin "6") (pinfunction "6_6") (pintype "passive"))
    )
    (net (code "145") (name "/PG11") (class "Default")
      (node (ref "P7") (pin "18") (pinfunction "18_18") (pintype "passive"))
      (node (ref "R49") (pin "1") (pinfunction "1_1") (pintype "passive"))
    )
    (net (code "146") (name "/PG15") (class "Default")
      (node (ref "P7") (pin "12") (pinfunction "12_12") (pintype "passive"))
    )
    (net (code "147") (name "/RESET") (class "Default")
      (node (ref "P6") (pin "20") (pinfunction "20_20") (pintype "passive"))
    )
    (net (code "148") (name "/RS485_RE") (class "Default")
      (node (ref "P7") (pin "42") (pinfunction "42_42") (pintype "passive"))
      (node (ref "U5") (pin "2") (pinfunction "~{RE}_2") (pintype "passive"))
      (node (ref "U5") (pin "3") (pinfunction "DE_3") (pintype "passive"))
    )
    (net (code "149") (name "/SDCLK") (class "Default")
      (node (ref "C2") (pin "2") (pinfunction "2_2") (pintype "passive"))
      (node (ref "CON1") (pin "5") (pinfunction "CLK_5") (pintype "passive"))
      (node (ref "P7") (pin "31") (pinfunction "31_31") (pintype "passive"))
      (node (ref "R20") (pin "2") (pinfunction "2_2") (pintype "passive"))
    )
    (net (code "150") (name "/SDCMD") (class "Default")
      (node (ref "CON1") (pin "2") (pinfunction "CMD_2") (pintype "passive"))
      (node (ref "P7") (pin "28") (pinfunction "28_28") (pintype "passive"))
      (node (ref "R21") (pin "2") (pinfunction "2_2") (pintype "passive"))
    )
    (net (code "151") (name "/SDDATA0") (class "Default")
      (node (ref "CON1") (pin "7") (pinfunction "DAT0_7") (pintype "passive"))
      (node (ref "P7") (pin "38") (pinfunction "38_38") (pintype "passive"))
      (node (ref "R19") (pin "2") (pinfunction "2_2") (pintype "passive"))
    )
    (net (code "152") (name "/SDDATA1") (class "Default")
      (node (ref "CON1") (pin "8") (pinfunction "DAT1_8") (pintype "passive"))
      (node (ref "P7") (pin "37") (pinfunction "37_37") (pintype "passive"))
      (node (ref "R18") (pin "2") (pinfunction "2_2") (pintype "passive"))
    )
    (net (code "153") (name "/SDDATA2") (class "Default")
      (node (ref "CON1") (pin "9") (pinfunction "DAT2_9") (pintype "passive"))
      (node (ref "P7") (pin "33") (pinfunction "33_33") (pintype "passive"))
      (node (ref "R23") (pin "2") (pinfunction "2_2") (pintype "passive"))
    )
    (net (code "154") (name "/SDDATA3") (class "Default")
      (node (ref "CON1") (pin "1") (pinfunction "CD/DAT3_1") (pintype "passive"))
      (node (ref "P7") (pin "32") (pinfunction "32_32") (pintype "passive"))
      (node (ref "R22") (pin "2") (pinfunction "2_2") (pintype "passive"))
    )
    (net (code "155") (name "/TPRX+") (class "Default")
      (node (ref "J1") (pin "1") (pinfunction "TD+_1") (pintype "passive"))
      (node (ref "R42") (pin "2") (pinfunction "2_2") (pintype "passive"))
      (node (ref "U4") (pin "3") (pinfunction "RX+_3") (pintype "passive"))
    )
    (net (code "156") (name "/TPRX-") (class "Default")
      (node (ref "J1") (pin "2") (pinfunction "TD-_2") (pintype "passive"))
      (node (ref "R43") (pin "2") (pinfunction "2_2") (pintype "passive"))
      (node (ref "U4") (pin "4") (pinfunction "RX-_4") (pintype "passive"))
    )
    (net (code "157") (name "/TPTX+") (class "Default")
      (node (ref "J1") (pin "3") (pinfunction "RD+_3") (pintype "passive"))
      (node (ref "R44") (pin "2") (pinfunction "2_2") (pintype "passive"))
      (node (ref "U4") (pin "7") (pinfunction "TX+_7") (pintype "passive"))
    )
    (net (code "158") (name "/TPTX-") (class "Default")
      (node (ref "J1") (pin "6") (pinfunction "RD-_6") (pintype "passive"))
      (node (ref "R45") (pin "2") (pinfunction "2_2") (pintype "passive"))
      (node (ref "U4") (pin "8") (pinfunction "TX-_8") (pintype "passive"))
    )
    (net (code "159") (name "/USART1_RX") (class "Default")
      (node (ref "P7") (pin "34") (pinfunction "34_34") (pintype "passive"))
    )
    (net (code "160") (name "/USART1_TX") (class "Default")
      (node (ref "P7") (pin "35") (pinfunction "35_35") (pintype "passive"))
    )
    (net (code "161") (name "/USART3_RX") (class "Default")
      (node (ref "P6") (pin "56") (pinfunction "56_56") (pintype "passive"))
      (node (ref "R32") (pin "1") (pinfunction "1_1") (pintype "passive"))
      (node (ref "U5") (pin "1") (pinfunction "RO_1") (pintype "passive"))
    )
    (net (code "162") (name "/USART3_TX") (class "Default")
      (node (ref "P6") (pin "55") (pinfunction "55_55") (pintype "passive"))
      (node (ref "R31") (pin "1") (pinfunction "1_1") (pintype "passive"))
      (node (ref "U5") (pin "4") (pinfunction "DI_4") (pintype "passive"))
    )
    (net (code "163") (name "/VOUT1") (class "Default")
      (node (ref "D4") (pin "2") (pinfunction "K_2") (pintype "passive"))
      (node (ref "D5") (pin "2") (pinfunction "K_2") (pintype "passive"))
      (node (ref "P5") (pin "1") (pinfunction "1_1") (pintype "passive"))
      (node (ref "P5") (pin "10") (pinfunction "10_10") (pintype "passive"))
      (node (ref "P5") (pin "12") (pinfunction "12_12") (pintype "passive"))
      (node (ref "P5") (pin "14") (pinfunction "14_14") (pintype "passive"))
      (node (ref "P5") (pin "16") (pinfunction "16_16") (pintype "passive"))
      (node (ref "P5") (pin "18") (pinfunction "18_18") (pintype "passive"))
      (node (ref "P5") (pin "19") (pinfunction "19_19") (pintype "passive"))
      (node (ref "P5") (pin "2") (pinfunction "2_2") (pintype "passive"))
      (node (ref "P5") (pin "20") (pinfunction "20_20") (pintype "passive"))
      (node (ref "P5") (pin "4") (pinfunction "4_4") (pintype "passive"))
      (node (ref "P5") (pin "6") (pinfunction "6_6") (pintype "passive"))
      (node (ref "P5") (pin "8") (pinfunction "8_8") (pintype "passive"))
    )
    (net (code "164") (name "/WP_SD") (class "Default")
      (node (ref "R27") (pin "2") (pinfunction "2_2") (pintype "passive"))
    )
    (net (code "165") (name "/WP_SD_1") (class "Default")
      (node (ref "CON1") (pin "10") (pinfunction "WP_10") (pintype "passive"))
      (node (ref "R24") (pin "2") (pinfunction "2_2") (pintype "passive"))
      (node (ref "R26") (pin "1") (pinfunction "1_1") (pintype "passive"))
      (node (ref "R27") (pin "1") (pinfunction "1_1") (pintype "passive"))
    )
    (net (code "166") (name "/nCD_SD") (class "Default")
      (node (ref "CON1") (pin "11") (pinfunction "nCD_11") (pintype "passive"))
      (node (ref "R25") (pin "2") (pinfunction "2_2") (pintype "passive"))
    )
    (net (code "167") (name "GND") (class "Default")
      (node (ref "C1") (pin "2") (pinfunction "2_2") (pintype "passive"))
      (node (ref "C10") (pin "1") (pinfunction "1_1") (pintype "passive"))
      (node (ref "C11") (pin "1") (pinfunction "1_1") (pintype "passive"))
      (node (ref "C12") (pin "2") (pinfunction "GND_2") (pintype "passive"))
      (node (ref "C13") (pin "1") (pinfunction "1_1") (pintype "passive"))
      (node (ref "C14") (pin "1") (pinfunction "1_1") (pintype "passive"))
      (node (ref "C15") (pin "1") (pinfunction "1_1") (pintype "passive"))
      (node (ref "C16") (pin "1") (pinfunction "1_1") (pintype "passive"))
      (node (ref "C17") (pin "2") (pinfunction "2_2") (pintype "passive"))
      (node (ref "C18") (pin "2") (pinfunction "2_2") (pintype "passive"))
      (node (ref "C19") (pin "1") (pinfunction "1_1") (pintype "passive"))
      (node (ref "C2") (pin "1") (pinfunction "1_1") (pintype "passive"))
      (node (ref "C20") (pin "1") (pinfunction "1_1") (pintype "passive"))
      (node (ref "C3") (pin "1") (pinfunction "1_1") (pintype "passive"))
      (node (ref "C4") (pin "1") (pinfunction "1_1") (pintype "passive"))
      (node (ref "C5") (pin "2") (pinfunction "GND_2") (pintype "passive"))
      (node (ref "C6") (pin "2") (pintype "passive"))
      (node (ref "C7") (pin "2") (pinfunction "2_2") (pintype "passive"))
      (node (ref "C8") (pin "2") (pinfunction "2_2") (pintype "passive"))
      (node (ref "C9") (pin "1") (pinfunction "1_1") (pintype "passive"))
      (node (ref "CON1") (pin "12") (pinfunction "PAD1_12") (pintype "passive"))
      (node (ref "CON1") (pin "13") (pinfunction "PAD2_13") (pintype "passive"))
      (node (ref "CON1") (pin "14") (pinfunction "PAD3_14") (pintype "passive"))
      (node (ref "CON1") (pin "15") (pinfunction "PAD4_15") (pintype "passive"))
      (node (ref "CON1") (pin "3") (pinfunction "VSS1_3") (pintype "passive"))
      (node (ref "CON1") (pin "6") (pinfunction "VSS2_6") (pintype "passive"))
      (node (ref "CT1") (pin "2") (pinfunction "Negative_2") (pintype "passive"))
      (node (ref "CT2") (pin "2") (pinfunction "2_2") (pintype "passive"))
      (node (ref "D1") (pin "3") (pinfunction "3_3") (pintype "passive"))
      (node (ref "D2") (pin "2") (pinfunction "T-_2") (pintype "passive"))
      (node (ref "DE1") (pin "1") (pinfunction "A_1") (pintype "passive"))
      (node (ref "DE10") (pin "1") (pinfunction "A_1") (pintype "passive"))
      (node (ref "DE11") (pin "1") (pinfunction "A_1") (pintype "passive"))
      (node (ref "DE12") (pin "1") (pinfunction "A_1") (pintype "passive"))
      (node (ref "DE13") (pin "1") (pinfunction "A_1") (pintype "passive"))
      (node (ref "DE14") (pin "1") (pinfunction "A_1") (pintype "passive"))
      (node (ref "DE15") (pin "1") (pinfunction "A_1") (pintype "passive"))
      (node (ref "DE16") (pin "1") (pinfunction "A_1") (pintype "passive"))
      (node (ref "DE2") (pin "1") (pinfunction "A_1") (pintype "passive"))
      (node (ref "DE3") (pin "1") (pinfunction "A_1") (pintype "passive"))
      (node (ref "DE4") (pin "1") (pinfunction "A_1") (pintype "passive"))
      (node (ref "DE5") (pin "1") (pinfunction "A_1") (pintype "passive"))
      (node (ref "DE6") (pin "1") (pinfunction "A_1") (pintype "passive"))
      (node (ref "DE7") (pin "1") (pinfunction "A_1") (pintype "passive"))
      (node (ref "DE8") (pin "1") (pinfunction "A_1") (pintype "passive"))
      (node (ref "DE9") (pin "1") (pinfunction "A_1") (pintype "passive"))
      (node (ref "J1") (pin "8") (pinfunction "CHS_GND_8") (pintype "passive"))
      (node (ref "LED1") (pin "2") (pinfunction "K_2") (pintype "passive"))
      (node (ref "LED17") (pin "2") (pinfunction "K_2") (pintype "passive"))
      (node (ref "LED18") (pin "2") (pinfunction "K_2") (pintype "passive"))
      (node (ref "LED19") (pin "2") (pinfunction "K_2") (pintype "passive"))
      (node (ref "LED2") (pin "2") (pinfunction "K_2") (pintype "passive"))
      (node (ref "LED20") (pin "2") (pinfunction "K_2") (pintype "passive"))
      (node (ref "LED3") (pin "2") (pinfunction "K_2") (pintype "passive"))
      (node (ref "LED33") (pin "2") (pinfunction "K_2") (pintype "passive"))
      (node (ref "LED34") (pin "2") (pinfunction "K_2") (pintype "passive"))
      (node (ref "LED35") (pin "2") (pinfunction "K_2") (pintype "passive"))
      (node (ref "LED36") (pin "2") (pinfunction "K_2") (pintype "passive"))
      (node (ref "LED37") (pin "2") (pinfunction "K_2") (pintype "passive"))
      (node (ref "LED38") (pin "2") (pinfunction "K_2") (pintype "passive"))
      (node (ref "LED39") (pin "2") (pinfunction "K_2") (pintype "passive"))
      (node (ref "LED4") (pin "2") (pinfunction "K_2") (pintype "passive"))
      (node (ref "LED40") (pin "2") (pinfunction "K_2") (pintype "passive"))
      (node (ref "P1") (pin "9") (pinfunction "9_9") (pintype "passive"))
      (node (ref "P2") (pin "17") (pinfunction "17_17") (pintype "passive"))
      (node (ref "P3") (pin "3") (pinfunction "3_3") (pintype "passive"))
      (node (ref "P4") (pin "17") (pinfunction "17_17") (pintype "passive"))
      (node (ref "P4") (pin "19") (pinfunction "19_19") (pintype "passive"))
      (node (ref "P5") (pin "11") (pinfunction "11_11") (pintype "passive"))
      (node (ref "P5") (pin "13") (pinfunction "13_13") (pintype "passive"))
      (node (ref "P5") (pin "15") (pinfunction "15_15") (pintype "passive"))
      (node (ref "P5") (pin "17") (pinfunction "17_17") (pintype "passive"))
      (node (ref "P5") (pin "3") (pinfunction "3_3") (pintype "passive"))
      (node (ref "P5") (pin "5") (pinfunction "5_5") (pintype "passive"))
      (node (ref "P5") (pin "7") (pinfunction "7_7") (pintype "passive"))
      (node (ref "P5") (pin "9") (pinfunction "9_9") (pintype "passive"))
      (node (ref "P6") (pin "13") (pinfunction "13_13") (pintype "passive"))
      (node (ref "P6") (pin "57") (pinfunction "57_57") (pintype "passive"))
      (node (ref "P6") (pin "58") (pinfunction "58_58") (pintype "passive"))
      (node (ref "P7") (pin "13") (pinfunction "13_13") (pintype "passive"))
      (node (ref "P7") (pin "2") (pinfunction "2_2") (pintype "passive"))
      (node (ref "P7") (pin "24") (pinfunction "24_24") (pintype "passive"))
      (node (ref "P8") (pin "3") (pinfunction "3_3") (pintype "passive"))
      (node (ref "P9") (pin "3") (pinfunction "3_3") (pintype "passive"))
      (node (ref "R26") (pin "2") (pinfunction "2_2") (pintype "passive"))
      (node (ref "R33") (pin "2") (pinfunction "2_2") (pintype "passive"))
      (node (ref "R35") (pin "1") (pinfunction "1_1") (pintype "passive"))
      (node (ref "R38") (pin "2") (pinfunction "2_2") (pintype "passive"))
      (node (ref "R39") (pin "1") (pinfunction "1_1") (pintype "passive"))
      (node (ref "TL1") (pin "11") (pinfunction "E_11") (pintype "passive"))
      (node (ref "TL1") (pin "13") (pinfunction "E_13") (pintype "passive"))
      (node (ref "TL1") (pin "15") (pinfunction "E_15") (pintype "passive"))
      (node (ref "TL1") (pin "9") (pinfunction "E_9") (pintype "passive"))
      (node (ref "TL2") (pin "11") (pinfunction "E_11") (pintype "passive"))
      (node (ref "TL2") (pin "13") (pinfunction "E_13") (pintype "passive"))
      (node (ref "TL2") (pin "15") (pinfunction "E_15") (pintype "passive"))
      (node (ref "TL2") (pin "9") (pinfunction "E_9") (pintype "passive"))
      (node (ref "TL3") (pin "11") (pinfunction "E_11") (pintype "passive"))
      (node (ref "TL3") (pin "13") (pinfunction "E_13") (pintype "passive"))
      (node (ref "TL3") (pin "15") (pinfunction "E_15") (pintype "passive"))
      (node (ref "TL3") (pin "9") (pinfunction "E_9") (pintype "passive"))
      (node (ref "TL4") (pin "11") (pinfunction "E_11") (pintype "passive"))
      (node (ref "TL4") (pin "13") (pinfunction "E_13") (pintype "passive"))
      (node (ref "TL4") (pin "15") (pinfunction "E_15") (pintype "passive"))
      (node (ref "TL4") (pin "9") (pinfunction "E_9") (pintype "passive"))
      (node (ref "TL5") (pin "11") (pinfunction "E_11") (pintype "passive"))
      (node (ref "TL5") (pin "13") (pinfunction "E_13") (pintype "passive"))
      (node (ref "TL5") (pin "15") (pinfunction "E_15") (pintype "passive"))
      (node (ref "TL5") (pin "9") (pinfunction "E_9") (pintype "passive"))
      (node (ref "TL6") (pin "11") (pinfunction "E_11") (pintype "passive"))
      (node (ref "TL6") (pin "13") (pinfunction "E_13") (pintype "passive"))
      (node (ref "TL6") (pin "15") (pinfunction "E_15") (pintype "passive"))
      (node (ref "TL6") (pin "9") (pinfunction "E_9") (pintype "passive"))
      (node (ref "U1") (pin "2") (pinfunction "GND_2") (pintype "passive"))
      (node (ref "U1") (pin "8") (pinfunction "S_8") (pintype "passive"))
      (node (ref "U2") (pin "3") (pinfunction "GND_3") (pintype "power_in"))
      (node (ref "U2") (pin "5") (pinfunction "~{ON}/OFF_5") (pintype "input"))
      (node (ref "U2") (pin "6") (pinfunction "GND_6") (pintype "passive"))
      (node (ref "U4") (pin "15") (pinfunction "GND_15") (pintype "passive"))
      (node (ref "U4") (pin "33") (pinfunction "GND_33") (pintype "passive"))
      (node (ref "U4") (pin "41") (pinfunction "TEST_41") (pintype "passive"))
      (node (ref "U4") (pin "45") (pinfunction "GND_45") (pintype "passive"))
      (node (ref "U4") (pin "47") (pinfunction "GND_47") (pintype "passive"))
      (node (ref "U4") (pin "48") (pinfunction "BGND_48") (pintype "passive"))
      (node (ref "U4") (pin "5") (pinfunction "GND_5") (pintype "passive"))
      (node (ref "U4") (pin "6") (pinfunction "GND_6") (pintype "passive"))
      (node (ref "U5") (pin "5") (pinfunction "GND_5") (pintype "passive"))
      (node (ref "U6") (pin "1") (pinfunction "GND_1") (pintype "passive"))
      (node (ref "V1") (pin "1") (pinfunction "A_1") (pintype "passive"))
    )
    (net (code "168") (name "Net-(C8-Pad1)") (class "Default")
      (node (ref "C8") (pin "1") (pinfunction "1_1") (pintype "passive"))
      (node (ref "U4") (pin "9") (pinfunction "VDD25_9") (pintype "passive"))
    )
    (net (code "169") (name "Net-(C13-Pad2)") (class "Default")
      (node (ref "C13") (pin "2") (pinfunction "2_2") (pintype "passive"))
      (node (ref "C14") (pin "2") (pinfunction "2_2") (pintype "passive"))
      (node (ref "C15") (pin "2") (pinfunction "2_2") (pintype "passive"))
      (node (ref "C16") (pin "2") (pinfunction "2_2") (pintype "passive"))
      (node (ref "FB1") (pin "1") (pinfunction "1_1") (pintype "passive"))
      (node (ref "U4") (pin "23") (pinfunction "VDD_23") (pintype "passive"))
      (node (ref "U4") (pin "30") (pinfunction "VDD_30") (pintype "passive"))
      (node (ref "U4") (pin "42") (pinfunction "VDD_42") (pintype "passive"))
    )
    (net (code "170") (name "Net-(C19-Pad2)") (class "Default")
      (node (ref "C19") (pin "2") (pinfunction "2_2") (pintype "passive"))
      (node (ref "R42") (pin "1") (pinfunction "1_1") (pintype "passive"))
      (node (ref "R43") (pin "1") (pinfunction "1_1") (pintype "passive"))
    )
    (net (code "171") (name "Net-(C20-Pad2)") (class "Default")
      (node (ref "C20") (pin "2") (pinfunction "2_2") (pintype "passive"))
      (node (ref "R44") (pin "1") (pinfunction "1_1") (pintype "passive"))
      (node (ref "R45") (pin "1") (pinfunction "1_1") (pintype "passive"))
    )
    (net (code "172") (name "Net-(D2-B-)") (class "Default")
      (node (ref "D2") (pin "1") (pinfunction "B-_1") (pintype "passive"))
      (node (ref "R29") (pin "1") (pinfunction "1_1") (pintype "passive"))
    )
    (net (code "173") (name "Net-(D3-K)") (class "Default")
      (node (ref "D3") (pin "2") (pinfunction "K_2") (pintype "passive"))
      (node (ref "U4") (pin "34") (pinfunction "INT_34") (pintype "passive"))
    )
    (net (code "174") (name "Net-(LED1-A)") (class "Default")
      (node (ref "LED1") (pin "1") (pinfunction "A_1") (pintype "passive"))
      (node (ref "RE1") (pin "2") (pinfunction "2_2") (pintype "passive"))
    )
    (net (code "175") (name "Net-(LED2-A)") (class "Default")
      (node (ref "LED2") (pin "1") (pinfunction "A_1") (pintype "passive"))
      (node (ref "RE2") (pin "2") (pinfunction "2_2") (pintype "passive"))
    )
    (net (code "176") (name "Net-(LED3-A)") (class "Default")
      (node (ref "LED3") (pin "1") (pinfunction "A_1") (pintype "passive"))
      (node (ref "RE3") (pin "2") (pinfunction "2_2") (pintype "passive"))
    )
    (net (code "177") (name "Net-(LED4-A)") (class "Default")
      (node (ref "LED4") (pin "1") (pinfunction "A_1") (pintype "passive"))
      (node (ref "RE4") (pin "2") (pinfunction "2_2") (pintype "passive"))
    )
    (net (code "178") (name "Net-(LED5-A)") (class "Default")
      (node (ref "LED5") (pin "1") (pinfunction "A_1") (pintype "passive"))
      (node (ref "TL1") (pin "2") (pinfunction "K_2") (pintype "passive"))
    )
    (net (code "179") (name "Net-(LED5-K)") (class "Default")
      (node (ref "LED5") (pin "2") (pinfunction "K_2") (pintype "passive"))
      (node (ref "RH1") (pin "1") (pinfunction "1_1") (pintype "passive"))
    )
    (net (code "180") (name "Net-(LED6-A)") (class "Default")
      (node (ref "LED6") (pin "1") (pinfunction "A_1") (pintype "passive"))
      (node (ref "TL2") (pin "2") (pinfunction "K_2") (pintype "passive"))
    )
    (net (code "181") (name "Net-(LED6-K)") (class "Default")
      (node (ref "LED6") (pin "2") (pinfunction "K_2") (pintype "passive"))
      (node (ref "RH2") (pin "1") (pinfunction "1_1") (pintype "passive"))
    )
    (net (code "182") (name "Net-(LED7-A)") (class "Default")
      (node (ref "LED7") (pin "1") (pinfunction "A_1") (pintype "passive"))
      (node (ref "RH3") (pin "1") (pinfunction "1_1") (pintype "passive"))
    )
    (net (code "183") (name "Net-(LED7-K)") (class "Default")
      (node (ref "LED7") (pin "2") (pinfunction "K_2") (pintype "passive"))
      (node (ref "TL3") (pin "7") (pinfunction "A_7") (pintype "passive"))
    )
    (net (code "184") (name "Net-(LED8-A)") (class "Default")
      (node (ref "LED8") (pin "1") (pinfunction "A_1") (pintype "passive"))
      (node (ref "TL1") (pin "4") (pinfunction "K_4") (pintype "passive"))
    )
    (net (code "185") (name "Net-(LED8-K)") (class "Default")
      (node (ref "LED8") (pin "2") (pinfunction "K_2") (pintype "passive"))
      (node (ref "RH4") (pin "1") (pinfunction "1_1") (pintype "passive"))
    )
    (net (code "186") (name "Net-(LED9-A)") (class "Default")
      (node (ref "LED9") (pin "1") (pinfunction "A_1") (pintype "passive"))
      (node (ref "TL2") (pin "4") (pinfunction "K_4") (pintype "passive"))
    )
    (net (code "187") (name "Net-(LED9-K)") (class "Default")
      (node (ref "LED9") (pin "2") (pinfunction "K_2") (pintype "passive"))
      (node (ref "RH5") (pin "1") (pinfunction "1_1") (pintype "passive"))
    )
    (net (code "188") (name "Net-(LED10-A)") (class "Default")
      (node (ref "LED10") (pin "1") (pinfunction "A_1") (pintype "passive"))
      (node (ref "RH6") (pin "1") (pinfunction "1_1") (pintype "passive"))
    )
    (net (code "189") (name "Net-(LED10-K)") (class "Default")
      (node (ref "LED10") (pin "2") (pinfunction "K_2") (pintype "passive"))
      (node (ref "TL3") (pin "5") (pinfunction "A_5") (pintype "passive"))
    )
    (net (code "190") (name "Net-(LED11-A)") (class "Default")
      (node (ref "LED11") (pin "1") (pinfunction "A_1") (pintype "passive"))
      (node (ref "TL1") (pin "6") (pinfunction "K_6") (pintype "passive"))
    )
    (net (code "191") (name "Net-(LED11-K)") (class "Default")
      (node (ref "LED11") (pin "2") (pinfunction "K_2") (pintype "passive"))
      (node (ref "RH7") (pin "1") (pinfunction "1_1") (pintype "passive"))
    )
    (net (code "192") (name "Net-(LED12-A)") (class "Default")
      (node (ref "LED12") (pin "1") (pinfunction "A_1") (pintype "passive"))
      (node (ref "TL2") (pin "6") (pinfunction "K_6") (pintype "passive"))
    )
    (net (code "193") (name "Net-(LED12-K)") (class "Default")
      (node (ref "LED12") (pin "2") (pinfunction "K_2") (pintype "passive"))
      (node (ref "RH8") (pin "1") (pinfunction "1_1") (pintype "passive"))
    )
    (net (code "194") (name "Net-(LED13-A)") (class "Default")
      (node (ref "LED13") (pin "1") (pinfunction "A_1") (pintype "passive"))
      (node (ref "RH9") (pin "1") (pinfunction "1_1") (pintype "passive"))
    )
    (net (code "195") (name "Net-(LED13-K)") (class "Default")
      (node (ref "LED13") (pin "2") (pinfunction "K_2") (pintype "passive"))
      (node (ref "TL3") (pin "3") (pinfunction "A_3") (pintype "passive"))
    )
    (net (code "196") (name "Net-(LED14-A)") (class "Default")
      (node (ref "LED14") (pin "1") (pinfunction "A_1") (pintype "passive"))
      (node (ref "TL1") (pin "8") (pinfunction "K_8") (pintype "passive"))
    )
    (net (code "197") (name "Net-(LED14-K)") (class "Default")
      (node (ref "LED14") (pin "2") (pinfunction "K_2") (pintype "passive"))
      (node (ref "RH10") (pin "1") (pinfunction "1_1") (pintype "passive"))
    )
    (net (code "198") (name "Net-(LED15-A)") (class "Default")
      (node (ref "LED15") (pin "1") (pinfunction "A_1") (pintype "passive"))
      (node (ref "TL2") (pin "8") (pinfunction "K_8") (pintype "passive"))
    )
    (net (code "199") (name "Net-(LED15-K)") (class "Default")
      (node (ref "LED15") (pin "2") (pinfunction "K_2") (pintype "passive"))
      (node (ref "RH11") (pin "1") (pinfunction "1_1") (pintype "passive"))
    )
    (net (code "200") (name "Net-(LED16-A)") (class "Default")
      (node (ref "LED16") (pin "1") (pinfunction "A_1") (pintype "passive"))
      (node (ref "RH12") (pin "1") (pinfunction "1_1") (pintype "passive"))
    )
    (net (code "201") (name "Net-(LED16-K)") (class "Default")
      (node (ref "LED16") (pin "2") (pinfunction "K_2") (pintype "passive"))
      (node (ref "TL3") (pin "1") (pinfunction "A_1") (pintype "passive"))
    )
    (net (code "202") (name "Net-(LED17-A)") (class "Default")
      (node (ref "LED17") (pin "1") (pinfunction "A_1") (pintype "passive"))
      (node (ref "RE5") (pin "2") (pinfunction "2_2") (pintype "passive"))
    )
    (net (code "203") (name "Net-(LED18-A)") (class "Default")
      (node (ref "LED18") (pin "1") (pinfunction "A_1") (pintype "passive"))
      (node (ref "RE6") (pin "2") (pinfunction "2_2") (pintype "passive"))
    )
    (net (code "204") (name "Net-(LED19-A)") (class "Default")
      (node (ref "LED19") (pin "1") (pinfunction "A_1") (pintype "passive"))
      (node (ref "RE7") (pin "2") (pinfunction "2_2") (pintype "passive"))
    )
    (net (code "205") (name "Net-(LED20-A)") (class "Default")
      (node (ref "LED20") (pin "1") (pinfunction "A_1") (pintype "passive"))
      (node (ref "RE8") (pin "2") (pinfunction "2_2") (pintype "passive"))
    )
    (net (code "206") (name "Net-(LED21-A)") (class "Default")
      (node (ref "LED21") (pin "1") (pinfunction "A_1") (pintype "passive"))
      (node (ref "RH13") (pin "1") (pinfunction "1_1") (pintype "passive"))
    )
    (net (code "207") (name "Net-(LED21-K)") (class "Default")
      (node (ref "LED21") (pin "2") (pinfunction "K_2") (pintype "passive"))
      (node (ref "TL6") (pin "7") (pinfunction "A_7") (pintype "passive"))
    )
    (net (code "208") (name "Net-(LED22-A)") (class "Default")
      (node (ref "LED22") (pin "1") (pinfunction "A_1") (pintype "passive"))
      (node (ref "TL4") (pin "2") (pinfunction "K_2") (pintype "passive"))
    )
    (net (code "209") (name "Net-(LED22-K)") (class "Default")
      (node (ref "LED22") (pin "2") (pinfunction "K_2") (pintype "passive"))
      (node (ref "RH14") (pin "1") (pinfunction "1_1") (pintype "passive"))
    )
    (net (code "210") (name "Net-(LED23-A)") (class "Default")
      (node (ref "LED23") (pin "1") (pinfunction "A_1") (pintype "passive"))
      (node (ref "TL5") (pin "2") (pinfunction "K_2") (pintype "passive"))
    )
    (net (code "211") (name "Net-(LED23-K)") (class "Default")
      (node (ref "LED23") (pin "2") (pinfunction "K_2") (pintype "passive"))
      (node (ref "RH15") (pin "1") (pinfunction "1_1") (pintype "passive"))
    )
    (net (code "212") (name "Net-(LED24-A)") (class "Default")
      (node (ref "LED24") (pin "1") (pinfunction "A_1") (pintype "passive"))
      (node (ref "RH16") (pin "1") (pinfunction "1_1") (pintype "passive"))
    )
    (net (code "213") (name "Net-(LED24-K)") (class "Default")
      (node (ref "LED24") (pin "2") (pinfunction "K_2") (pintype "passive"))
      (node (ref "TL6") (pin "5") (pinfunction "A_5") (pintype "passive"))
    )
    (net (code "214") (name "Net-(LED25-A)") (class "Default")
      (node (ref "LED25") (pin "1") (pinfunction "A_1") (pintype "passive"))
      (node (ref "TL4") (pin "4") (pinfunction "K_4") (pintype "passive"))
    )
    (net (code "215") (name "Net-(LED25-K)") (class "Default")
      (node (ref "LED25") (pin "2") (pinfunction "K_2") (pintype "passive"))
      (node (ref "RH17") (pin "1") (pinfunction "1_1") (pintype "passive"))
    )
    (net (code "216") (name "Net-(LED26-A)") (class "Default")
      (node (ref "LED26") (pin "1") (pinfunction "A_1") (pintype "passive"))
      (node (ref "TL5") (pin "4") (pinfunction "K_4") (pintype "passive"))
    )
    (net (code "217") (name "Net-(LED26-K)") (class "Default")
      (node (ref "LED26") (pin "2") (pinfunction "K_2") (pintype "passive"))
      (node (ref "RH18") (pin "1") (pinfunction "1_1") (pintype "passive"))
    )
    (net (code "218") (name "Net-(LED27-A)") (class "Default")
      (node (ref "LED27") (pin "1") (pinfunction "A_1") (pintype "passive"))
      (node (ref "RH19") (pin "1") (pinfunction "1_1") (pintype "passive"))
    )
    (net (code "219") (name "Net-(LED27-K)") (class "Default")
      (node (ref "LED27") (pin "2") (pinfunction "K_2") (pintype "passive"))
      (node (ref "TL6") (pin "3") (pinfunction "A_3") (pintype "passive"))
    )
    (net (code "220") (name "Net-(LED28-A)") (class "Default")
      (node (ref "LED28") (pin "1") (pinfunction "A_1") (pintype "passive"))
      (node (ref "TL4") (pin "6") (pinfunction "K_6") (pintype "passive"))
    )
    (net (code "221") (name "Net-(LED28-K)") (class "Default")
      (node (ref "LED28") (pin "2") (pinfunction "K_2") (pintype "passive"))
      (node (ref "RH20") (pin "1") (pinfunction "1_1") (pintype "passive"))
    )
    (net (code "222") (name "Net-(LED29-A)") (class "Default")
      (node (ref "LED29") (pin "1") (pinfunction "A_1") (pintype "passive"))
      (node (ref "TL5") (pin "6") (pinfunction "K_6") (pintype "passive"))
    )
    (net (code "223") (name "Net-(LED29-K)") (class "Default")
      (node (ref "LED29") (pin "2") (pinfunction "K_2") (pintype "passive"))
      (node (ref "RH21") (pin "1") (pinfunction "1_1") (pintype "passive"))
    )
    (net (code "224") (name "Net-(LED30-A)") (class "Default")
      (node (ref "LED30") (pin "1") (pinfunction "A_1") (pintype "passive"))
      (node (ref "RH22") (pin "1") (pinfunction "1_1") (pintype "passive"))
    )
    (net (code "225") (name "Net-(LED30-K)") (class "Default")
      (node (ref "LED30") (pin "2") (pinfunction "K_2") (pintype "passive"))
      (node (ref "TL6") (pin "1") (pinfunction "A_1") (pintype "passive"))
    )
    (net (code "226") (name "Net-(LED31-A)") (class "Default")
      (node (ref "LED31") (pin "1") (pinfunction "A_1") (pintype "passive"))
      (node (ref "TL4") (pin "8") (pinfunction "K_8") (pintype "passive"))
    )
    (net (code "227") (name "Net-(LED31-K)") (class "Default")
      (node (ref "LED31") (pin "2") (pinfunction "K_2") (pintype "passive"))
      (node (ref "RH23") (pin "1") (pinfunction "1_1") (pintype "passive"))
    )
    (net (code "228") (name "Net-(LED32-A)") (class "Default")
      (node (ref "LED32") (pin "1") (pinfunction "A_1") (pintype "passive"))
      (node (ref "TL5") (pin "8") (pinfunction "K_8") (pintype "passive"))
    )
    (net (code "229") (name "Net-(LED32-K)") (class "Default")
      (node (ref "LED32") (pin "2") (pinfunction "K_2") (pintype "passive"))
      (node (ref "RH24") (pin "1") (pinfunction "1_1") (pintype "passive"))
    )
    (net (code "230") (name "Net-(LED33-A)") (class "Default")
      (node (ref "LED33") (pin "1") (pinfunction "A_1") (pintype "passive"))
      (node (ref "RE9") (pin "2") (pinfunction "2_2") (pintype "passive"))
    )
    (net (code "231") (name "Net-(LED34-A)") (class "Default")
      (node (ref "LED34") (pin "1") (pinfunction "A_1") (pintype "passive"))
      (node (ref "RE10") (pin "2") (pinfunction "2_2") (pintype "passive"))
    )
    (net (code "232") (name "Net-(LED35-A)") (class "Default")
      (node (ref "LED35") (pin "1") (pinfunction "A_1") (pintype "passive"))
      (node (ref "RE11") (pin "2") (pinfunction "2_2") (pintype "passive"))
    )
    (net (code "233") (name "Net-(LED36-A)") (class "Default")
      (node (ref "LED36") (pin "1") (pinfunction "A_1") (pintype "passive"))
      (node (ref "RE12") (pin "2") (pinfunction "2_2") (pintype "passive"))
    )
    (net (code "234") (name "Net-(LED37-A)") (class "Default")
      (node (ref "LED37") (pin "1") (pinfunction "A_1") (pintype "passive"))
      (node (ref "RE13") (pin "2") (pinfunction "2_2") (pintype "passive"))
    )
    (net (code "235") (name "Net-(LED38-A)") (class "Default")
      (node (ref "LED38") (pin "1") (pinfunction "A_1") (pintype "passive"))
      (node (ref "RE14") (pin "2") (pinfunction "2_2") (pintype "passive"))
    )
    (net (code "236") (name "Net-(LED39-A)") (class "Default")
      (node (ref "LED39") (pin "1") (pinfunction "A_1") (pintype "passive"))
      (node (ref "RE15") (pin "2") (pinfunction "2_2") (pintype "passive"))
    )
    (net (code "237") (name "Net-(LED40-A)") (class "Default")
      (node (ref "LED40") (pin "1") (pinfunction "A_1") (pintype "passive"))
      (node (ref "RE16") (pin "2") (pinfunction "2_2") (pintype "passive"))
    )
    (net (code "238") (name "Net-(LED41-K)") (class "Default")
      (node (ref "LED41") (pin "2") (pinfunction "K_2") (pintype "passive"))
      (node (ref "R31") (pin "2") (pinfunction "2_2") (pintype "passive"))
    )
    (net (code "239") (name "Net-(LED42-K)") (class "Default")
      (node (ref "LED42") (pin "2") (pinfunction "K_2") (pintype "passive"))
      (node (ref "R32") (pin "2") (pinfunction "2_2") (pintype "passive"))
    )
    (net (code "240") (name "Net-(QE1-Pad1)") (class "Default")
      (node (ref "QE1") (pin "1") (pinfunction "1_1") (pintype "passive"))
      (node (ref "R1") (pin "2") (pinfunction "2_2") (pintype "passive"))
    )
    (net (code "241") (name "Net-(QE2-Pad1)") (class "Default")
      (node (ref "QE2") (pin "1") (pinfunction "1_1") (pintype "passive"))
      (node (ref "R2") (pin "2") (pinfunction "2_2") (pintype "passive"))
    )
    (net (code "242") (name "Net-(QE3-Pad1)") (class "Default")
      (node (ref "QE3") (pin "1") (pinfunction "1_1") (pintype "passive"))
      (node (ref "R3") (pin "2") (pinfunction "2_2") (pintype "passive"))
    )
    (net (code "243") (name "Net-(QE4-Pad1)") (class "Default")
      (node (ref "QE4") (pin "1") (pinfunction "1_1") (pintype "passive"))
      (node (ref "R4") (pin "2") (pinfunction "2_2") (pintype "passive"))
    )
    (net (code "244") (name "Net-(QE5-Pad1)") (class "Default")
      (node (ref "QE5") (pin "1") (pinfunction "1_1") (pintype "passive"))
      (node (ref "R5") (pin "2") (pinfunction "2_2") (pintype "passive"))
    )
    (net (code "245") (name "Net-(QE6-Pad1)") (class "Default")
      (node (ref "QE6") (pin "1") (pinfunction "1_1") (pintype "passive"))
      (node (ref "R6") (pin "2") (pinfunction "2_2") (pintype "passive"))
    )
    (net (code "246") (name "Net-(QE7-Pad1)") (class "Default")
      (node (ref "QE7") (pin "1") (pinfunction "1_1") (pintype "passive"))
      (node (ref "R7") (pin "2") (pinfunction "2_2") (pintype "passive"))
    )
    (net (code "247") (name "Net-(QE8-Pad1)") (class "Default")
      (node (ref "QE8") (pin "1") (pinfunction "1_1") (pintype "passive"))
      (node (ref "R8") (pin "2") (pinfunction "2_2") (pintype "passive"))
    )
    (net (code "248") (name "Net-(QE9-Pad1)") (class "Default")
      (node (ref "QE9") (pin "1") (pinfunction "1_1") (pintype "passive"))
      (node (ref "R9") (pin "2") (pinfunction "2_2") (pintype "passive"))
    )
    (net (code "249") (name "Net-(QE10-Pad1)") (class "Default")
      (node (ref "QE10") (pin "1") (pinfunction "1_1") (pintype "passive"))
      (node (ref "R10") (pin "2") (pinfunction "2_2") (pintype "passive"))
    )
    (net (code "250") (name "Net-(QE11-Pad1)") (class "Default")
      (node (ref "QE11") (pin "1") (pinfunction "1_1") (pintype "passive"))
      (node (ref "R11") (pin "2") (pinfunction "2_2") (pintype "passive"))
    )
    (net (code "251") (name "Net-(QE12-Pad1)") (class "Default")
      (node (ref "QE12") (pin "1") (pinfunction "1_1") (pintype "passive"))
      (node (ref "R12") (pin "2") (pinfunction "2_2") (pintype "passive"))
    )
    (net (code "252") (name "Net-(QE13-Pad1)") (class "Default")
      (node (ref "QE13") (pin "1") (pinfunction "1_1") (pintype "passive"))
      (node (ref "R13") (pin "2") (pinfunction "2_2") (pintype "passive"))
    )
    (net (code "253") (name "Net-(QE14-Pad1)") (class "Default")
      (node (ref "QE14") (pin "1") (pinfunction "1_1") (pintype "passive"))
      (node (ref "R14") (pin "2") (pinfunction "2_2") (pintype "passive"))
    )
    (net (code "254") (name "Net-(QE15-Pad1)") (class "Default")
      (node (ref "QE15") (pin "1") (pinfunction "1_1") (pintype "passive"))
      (node (ref "R15") (pin "2") (pinfunction "2_2") (pintype "passive"))
    )
    (net (code "255") (name "Net-(QE16-Pad1)") (class "Default")
      (node (ref "QE16") (pin "1") (pinfunction "1_1") (pintype "passive"))
      (node (ref "R16") (pin "2") (pinfunction "2_2") (pintype "passive"))
    )
    (net (code "256") (name "Net-(U1-CAN_H)") (class "Default")
      (node (ref "P3") (pin "2") (pinfunction "2_2") (pintype "passive"))
      (node (ref "R17") (pin "1") (pinfunction "1_1") (pintype "passive"))
      (node (ref "U1") (pin "7") (pinfunction "CAN_H_7") (pintype "passive"))
    )
    (net (code "257") (name "Net-(U1-CAN_L)") (class "Default")
      (node (ref "P3") (pin "1") (pinfunction "1_1") (pintype "passive"))
      (node (ref "R17") (pin "2") (pinfunction "2_2") (pintype "passive"))
      (node (ref "U1") (pin "6") (pinfunction "CAN_L_6") (pintype "passive"))
    )
    (net (code "258") (name "Net-(U2-OUT)") (class "Default")
      (node (ref "L1") (pin "1") (pinfunction "1_1") (pintype "passive"))
      (node (ref "U2") (pin "2") (pinfunction "OUT_2") (pintype "power_in"))
      (node (ref "V1") (pin "2") (pinfunction "K_2") (pintype "passive"))
    )
    (net (code "259") (name "Net-(U4-BGRES)") (class "Default")
      (node (ref "R35") (pin "2") (pinfunction "2_2") (pintype "passive"))
      (node (ref "U4") (pin "1") (pinfunction "BGRES_1") (pintype "passive"))
    )
    (net (code "260") (name "Net-(U4-EEDCK)") (class "Default")
      (node (ref "R37") (pin "2") (pinfunction "2_2") (pintype "passive"))
      (node (ref "U4") (pin "20") (pinfunction "EEDCK_20") (pintype "passive"))
    )
    (net (code "261") (name "Net-(U4-EEDCS)") (class "Default")
      (node (ref "R36") (pin "2") (pinfunction "2_2") (pintype "passive"))
      (node (ref "U4") (pin "21") (pinfunction "EEDCS_21") (pintype "passive"))
    )
    (net (code "262") (name "Net-(U4-LED1)") (class "Default")
      (node (ref "R41") (pin "1") (pinfunction "1_1") (pintype "passive"))
      (node (ref "U4") (pin "39") (pinfunction "LED1_39") (pintype "passive"))
    )
    (net (code "263") (name "Net-(U4-LED2)") (class "Default")
      (node (ref "R40") (pin "1") (pinfunction "1_1") (pintype "passive"))
      (node (ref "U4") (pin "38") (pinfunction "LED2_38") (pintype "passive"))
    )
    (net (code "264") (name "Net-(U4-X1)") (class "Default")
      (node (ref "C18") (pin "1") (pinfunction "1_1") (pintype "passive"))
      (node (ref "U4") (pin "44") (pinfunction "X1_44") (pintype "passive"))
      (node (ref "Y1") (pin "2") (pinfunction "OSC2_2") (pintype "passive"))
    )
    (net (code "265") (name "Net-(U4-X2)") (class "Default")
      (node (ref "C17") (pin "1") (pinfunction "1_1") (pintype "passive"))
      (node (ref "U4") (pin "43") (pinfunction "X2_43") (pintype "passive"))
      (node (ref "Y1") (pin "1") (pinfunction "OSC1_1") (pintype "passive"))
    )
    (net (code "266") (name "P24V") (class "Default")
      (node (ref "C5") (pin "1") (pinfunction "VCC_1") (pintype "passive"))
      (node (ref "P2") (pin "18") (pinfunction "18_18") (pintype "passive"))
      (node (ref "QE1") (pin "3") (pinfunction "3_3") (pintype "passive"))
      (node (ref "QE10") (pin "3") (pinfunction "3_3") (pintype "passive"))
      (node (ref "QE11") (pin "3") (pinfunction "3_3") (pintype "passive"))
      (node (ref "QE12") (pin "3") (pinfunction "3_3") (pintype "passive"))
      (node (ref "QE13") (pin "3") (pinfunction "3_3") (pintype "passive"))
      (node (ref "QE14") (pin "3") (pinfunction "3_3") (pintype "passive"))
      (node (ref "QE15") (pin "3") (pinfunction "3_3") (pintype "passive"))
      (node (ref "QE16") (pin "3") (pinfunction "3_3") (pintype "passive"))
      (node (ref "QE2") (pin "3") (pinfunction "3_3") (pintype "passive"))
      (node (ref "QE3") (pin "3") (pinfunction "3_3") (pintype "passive"))
      (node (ref "QE4") (pin "3") (pinfunction "3_3") (pintype "passive"))
      (node (ref "QE5") (pin "3") (pinfunction "3_3") (pintype "passive"))
      (node (ref "QE6") (pin "3") (pinfunction "3_3") (pintype "passive"))
      (node (ref "QE7") (pin "3") (pinfunction "3_3") (pintype "passive"))
      (node (ref "QE8") (pin "3") (pinfunction "3_3") (pintype "passive"))
      (node (ref "QE9") (pin "3") (pinfunction "3_3") (pintype "passive"))
      (node (ref "U2") (pin "1") (pinfunction "IN_1") (pintype "power_in"))
    )
    (net (code "267") (name "PG") (class "Default")
      (node (ref "C7") (pin "1") (pinfunction "1_1") (pintype "passive"))
      (node (ref "J1") (pin "13") (pinfunction "SHILED_13") (pintype "passive"))
      (node (ref "J1") (pin "14") (pinfunction "SHILED_14") (pintype "passive"))
      (node (ref "R39") (pin "2") (pinfunction "2_2") (pintype "passive"))
    )
    (net (code "268") (name "VCC5V") (class "Default")
      (node (ref "C1") (pin "1") (pinfunction "1_1") (pintype "passive"))
      (node (ref "C10") (pin "2") (pinfunction "2_2") (pintype "passive"))
      (node (ref "C4") (pin "2") (pinfunction "2_2") (pintype "passive"))
      (node (ref "C6") (pin "1") (pintype "passive"))
      (node (ref "CT1") (pin "1") (pinfunction "Positive_1") (pintype "passive"))
      (node (ref "D4") (pin "1") (pinfunction "A_1") (pintype "passive"))
      (node (ref "D5") (pin "1") (pinfunction "A_1") (pintype "passive"))
      (node (ref "L1") (pin "2") (pinfunction "2_2") (pintype "passive"))
      (node (ref "P4") (pin "13") (pinfunction "13_13") (pintype "passive"))
      (node (ref "P4") (pin "15") (pinfunction "15_15") (pintype "passive"))
      (node (ref "P6") (pin "59") (pinfunction "59_59") (pintype "passive"))
      (node (ref "P6") (pin "60") (pinfunction "60_60") (pintype "passive"))
      (node (ref "P9") (pin "4") (pinfunction "4_4") (pintype "passive"))
      (node (ref "R29") (pin "2") (pinfunction "2_2") (pintype "passive"))
      (node (ref "TL1") (pin "1") (pinfunction "A_1") (pintype "passive"))
      (node (ref "TL1") (pin "3") (pinfunction "A_3") (pintype "passive"))
      (node (ref "TL1") (pin "5") (pinfunction "A_5") (pintype "passive"))
      (node (ref "TL1") (pin "7") (pinfunction "A_7") (pintype "passive"))
      (node (ref "TL2") (pin "1") (pinfunction "A_1") (pintype "passive"))
      (node (ref "TL2") (pin "3") (pinfunction "A_3") (pintype "passive"))
      (node (ref "TL2") (pin "5") (pinfunction "A_5") (pintype "passive"))
      (node (ref "TL2") (pin "7") (pinfunction "A_7") (pintype "passive"))
      (node (ref "TL4") (pin "1") (pinfunction "A_1") (pintype "passive"))
      (node (ref "TL4") (pin "3") (pinfunction "A_3") (pintype "passive"))
      (node (ref "TL4") (pin "5") (pinfunction "A_5") (pintype "passive"))
      (node (ref "TL4") (pin "7") (pinfunction "A_7") (pintype "passive"))
      (node (ref "TL5") (pin "1") (pinfunction "A_1") (pintype "passive"))
      (node (ref "TL5") (pin "3") (pinfunction "A_3") (pintype "passive"))
      (node (ref "TL5") (pin "5") (pinfunction "A_5") (pintype "passive"))
      (node (ref "TL5") (pin "7") (pinfunction "A_7") (pintype "passive"))
      (node (ref "U1") (pin "3") (pinfunction "VCC_3") (pintype "passive"))
      (node (ref "U2") (pin "4") (pinfunction "FB_4") (pintype "input"))
      (node (ref "U6") (pin "3") (pinfunction "IN_3") (pintype "passive"))
    )
    (net (code "269") (name "VDD25V") (class "Default")
      (node (ref "C9") (pin "2") (pinfunction "2_2") (pintype "passive"))
      (node (ref "CT2") (pin "1") (pinfunction "1_1") (pintype "passive"))
      (node (ref "J1") (pin "4") (pinfunction "TCT_4") (pintype "passive"))
      (node (ref "J1") (pin "5") (pinfunction "RCT_5") (pintype "passive"))
      (node (ref "U4") (pin "2") (pinfunction "VDD25_2") (pintype "passive"))
    )
    (net (code "270") (name "VDD33V") (class "Default")
      (node (ref "C11") (pin "2") (pinfunction "2_2") (pintype "passive"))
      (node (ref "C12") (pin "1") (pinfunction "VCC_1") (pintype "passive"))
      (node (ref "C3") (pin "2") (pinfunction "2_2") (pintype "passive"))
      (node (ref "CON1") (pin "4") (pinfunction "VDD_4") (pintype "passive"))
      (node (ref "FB1") (pin "2") (pinfunction "2_2") (pintype "passive"))
      (node (ref "J1") (pin "12") (pinfunction "LED(Y)_A_12") (pintype "passive"))
      (node (ref "J1") (pin "9") (pinfunction "LED(G)_A_9") (pintype "passive"))
      (node (ref "LED41") (pin "1") (pinfunction "A_1") (pintype "passive"))
      (node (ref "LED42") (pin "1") (pinfunction "A_1") (pintype "passive"))
      (node (ref "P4") (pin "21") (pinfunction "21_21") (pintype "passive"))
      (node (ref "P4") (pin "23") (pinfunction "23_23") (pintype "passive"))
      (node (ref "R18") (pin "1") (pinfunction "1_1") (pintype "passive"))
      (node (ref "R19") (pin "1") (pinfunction "1_1") (pintype "passive"))
      (node (ref "R20") (pin "1") (pinfunction "1_1") (pintype "passive"))
      (node (ref "R21") (pin "1") (pinfunction "1_1") (pintype "passive"))
      (node (ref "R22") (pin "1") (pinfunction "1_1") (pintype "passive"))
      (node (ref "R23") (pin "1") (pinfunction "1_1") (pintype "passive"))
      (node (ref "R24") (pin "1") (pinfunction "1_1") (pintype "passive"))
      (node (ref "R25") (pin "1") (pinfunction "1_1") (pintype "passive"))
      (node (ref "R28") (pin "2") (pinfunction "2_2") (pintype "passive"))
      (node (ref "R34") (pin "2") (pinfunction "2_2") (pintype "passive"))
      (node (ref "R36") (pin "1") (pinfunction "1_1") (pintype "passive"))
      (node (ref "R37") (pin "1") (pinfunction "1_1") (pintype "passive"))
      (node (ref "U5") (pin "8") (pinfunction "VCC_8") (pintype "passive"))
      (node (ref "U6") (pin "2") (pinfunction "OUT_2") (pintype "passive"))
      (node (ref "U6") (pin "4") (pinfunction "OUT_4") (pintype "passive"))
    )
    (net (code "271") (name "unconnected-(J1-NC-Pad7)") (class "Default")
      (node (ref "J1") (pin "7") (pinfunction "NC_7") (pintype "passive"))
    )
    (net (code "272") (name "unconnected-(P4-Pad9)") (class "Default")
      (node (ref "P4") (pin "9") (pinfunction "9_9") (pintype "passive"))
    )
    (net (code "273") (name "unconnected-(P4-Pad11)") (class "Default")
      (node (ref "P4") (pin "11") (pinfunction "11_11") (pintype "passive"))
    )
    (net (code "274") (name "unconnected-(P6-Pad14)") (class "Default")
      (node (ref "P6") (pin "14") (pinfunction "14_14") (pintype "passive"))
    )
    (net (code "275") (name "unconnected-(P6-Pad25)") (class "Default")
      (node (ref "P6") (pin "25") (pinfunction "25_25") (pintype "passive"))
    )
    (net (code "276") (name "unconnected-(P6-Pad26)") (class "Default")
      (node (ref "P6") (pin "26") (pinfunction "26_26") (pintype "passive"))
    )
    (net (code "277") (name "unconnected-(P7-Pad1)") (class "Default")
      (node (ref "P7") (pin "1") (pinfunction "1_1") (pintype "passive"))
    )
    (net (code "278") (name "unconnected-(P7-Pad14)") (class "Default")
      (node (ref "P7") (pin "14") (pinfunction "14_14") (pintype "passive"))
    )
    (net (code "279") (name "unconnected-(P7-Pad23)") (class "Default")
      (node (ref "P7") (pin "23") (pinfunction "23_23") (pintype "passive"))
    )
    (net (code "280") (name "unconnected-(P7-Pad41)") (class "Default")
      (node (ref "P7") (pin "41") (pinfunction "41_41") (pintype "passive"))
    )
    (net (code "281") (name "unconnected-(U1-VRef-Pad5)") (class "Default")
      (node (ref "U1") (pin "5") (pinfunction "VRef_5") (pintype "passive"))
    )
    (net (code "282") (name "unconnected-(U4-EEDIO-Pad19)") (class "Default")
      (node (ref "U4") (pin "19") (pinfunction "EEDIO_19") (pintype "passive"))
    )
    (net (code "283") (name "unconnected-(U4-SD-Pad46)") (class "Default")
      (node (ref "U4") (pin "46") (pinfunction "SD_46") (pintype "passive"))
    )
  )
)
